# Positive_Rail.net
KiCad netlist of a schematic drawn in Altium Designer
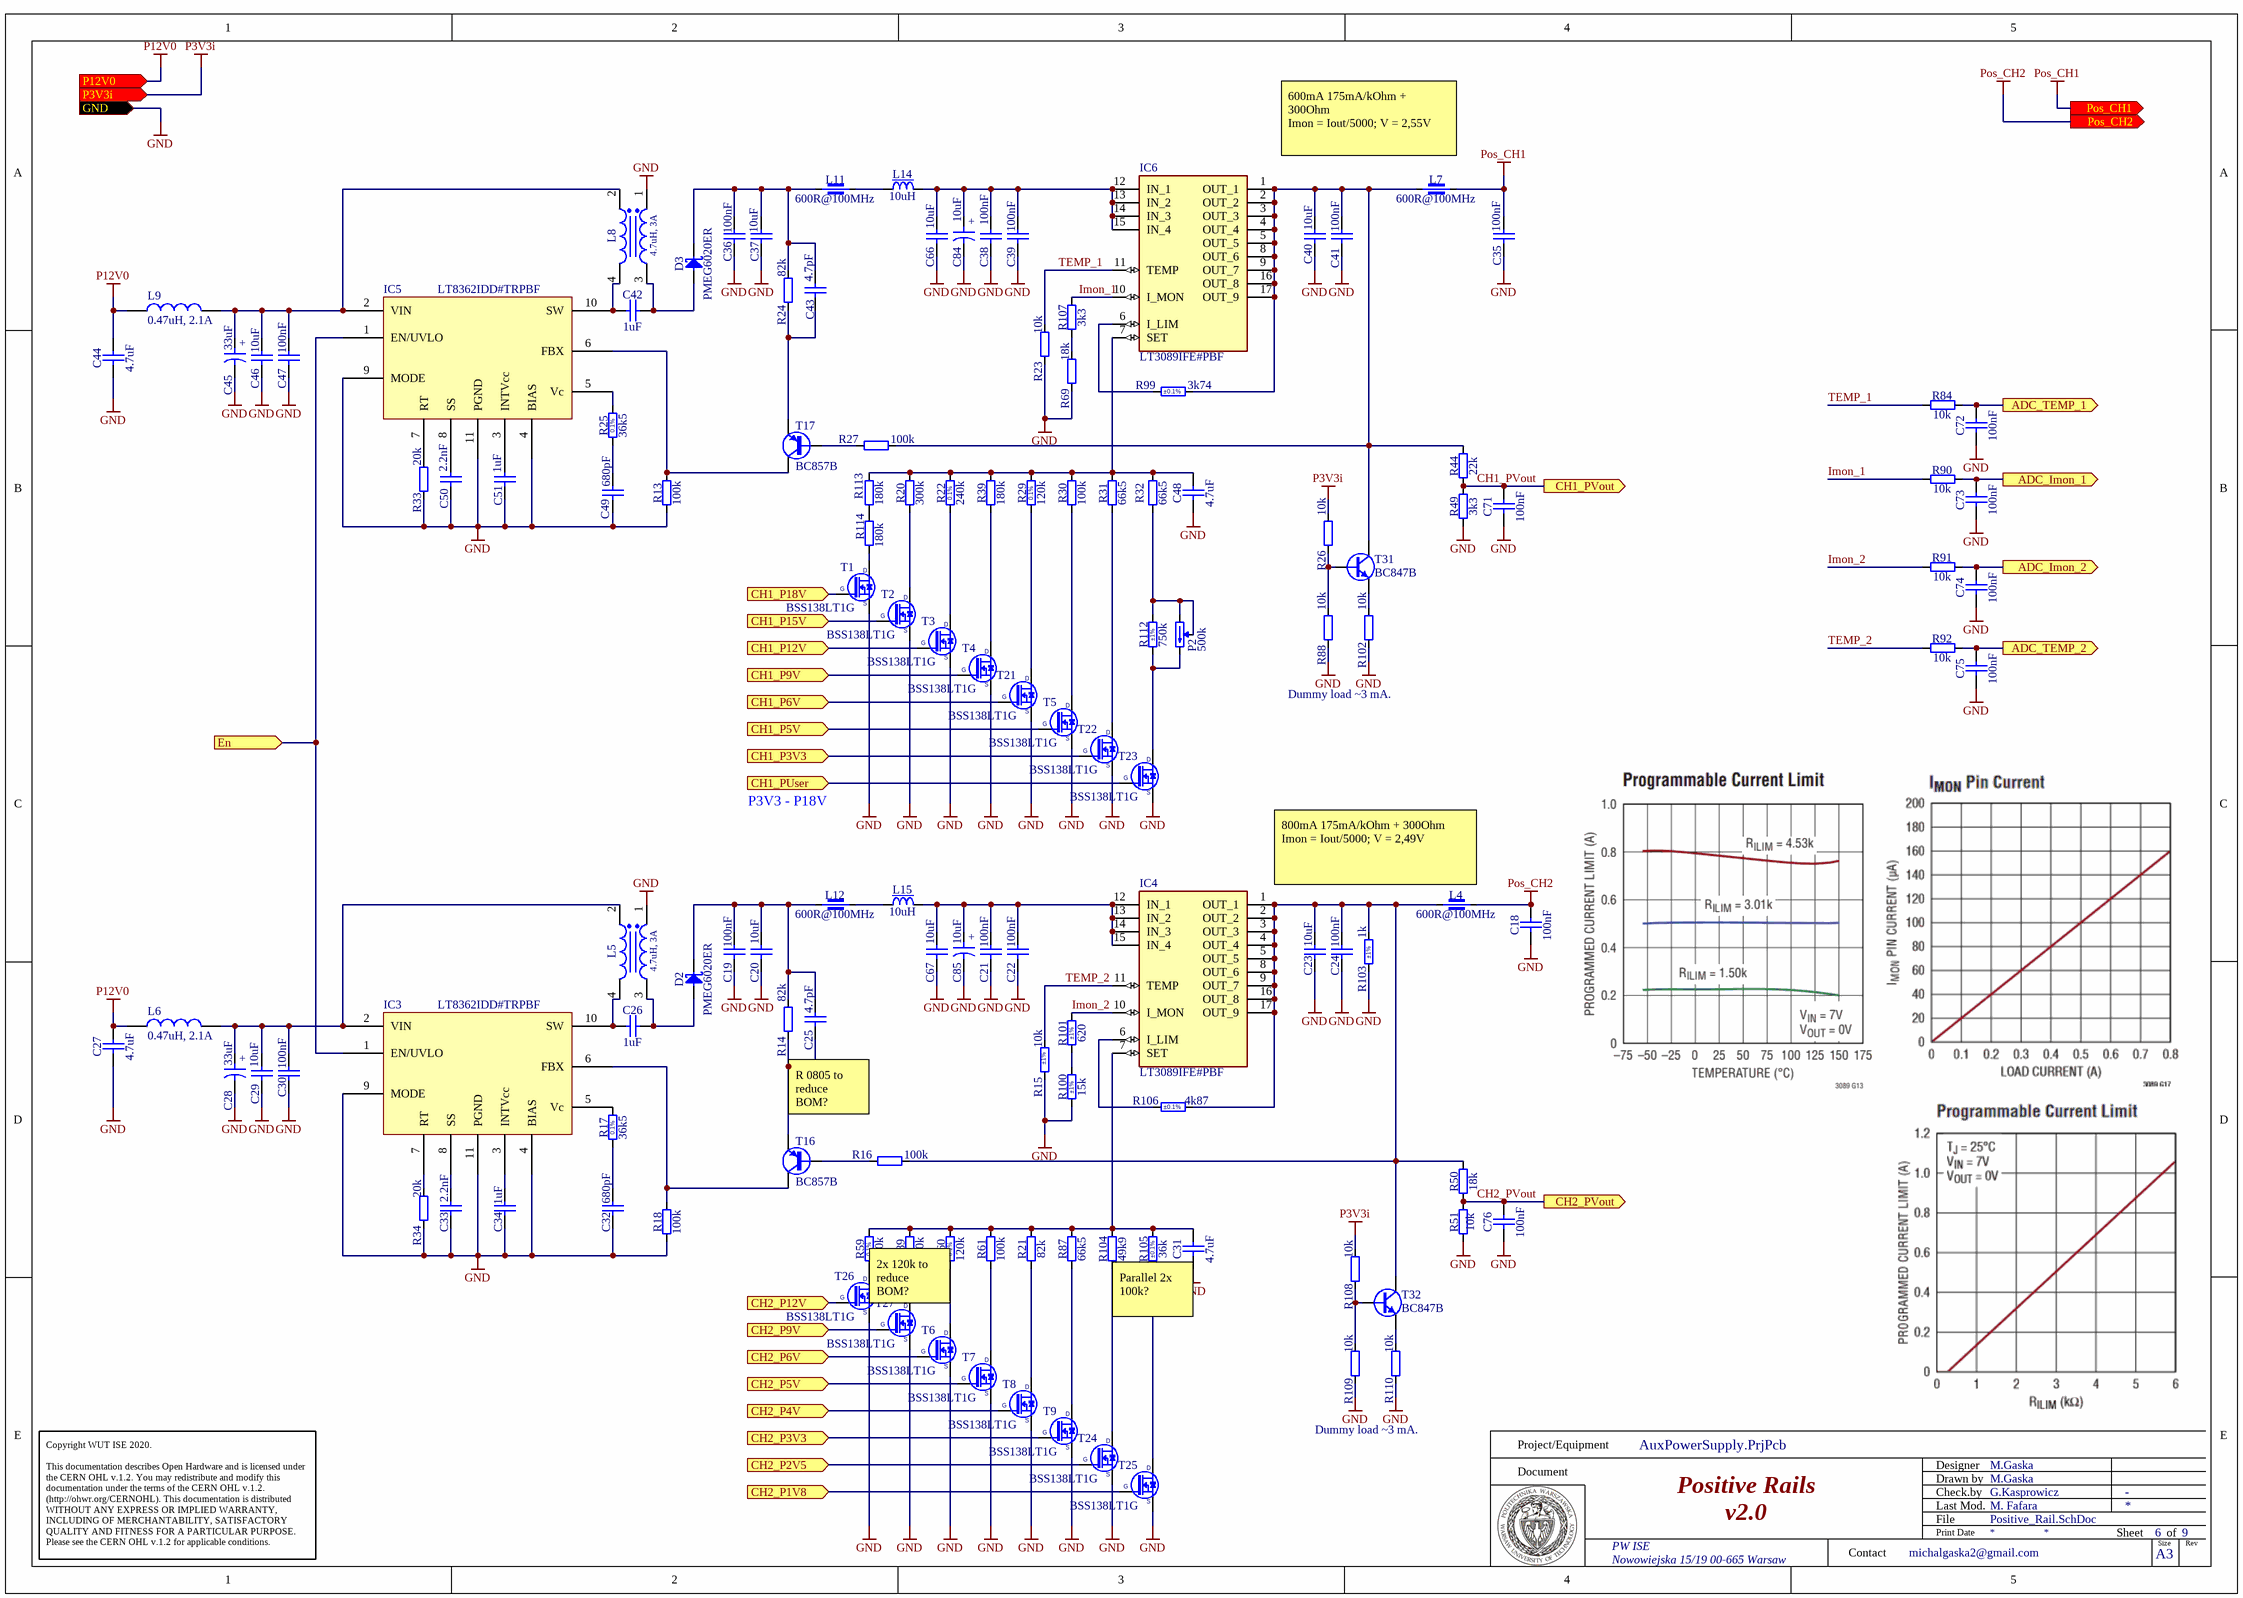
[diagram p0: Positive_Rail.SchDoc]

(export (version "E")
  (design (tool "Eeschema 10.0.6"))
  (components
    (comp (ref "C18")
      (value "100nF")
      (footprint "CAPC1608X87N")
      (description "Non-polarised capacitor")
      (fields
        (field (name "PART NUMBER") "CC0603_100NF_50V_10%_X5R")
        (field (name "VOLTAGE") "50V")
        (field (name "AUTHOR") "CERN DEM MR")
      )
      (libsource (lib "Capacitors") (part "Capacitor - non polarized"))
    )
    (comp (ref "C19")
      (value "100nF")
      (footprint "CAPC1608X87N")
      (description "Non-polarised capacitor")
      (fields
        (field (name "PART NUMBER") "CC0603_100NF_50V_10%_X5R")
        (field (name "VOLTAGE") "50V")
        (field (name "AUTHOR") "CERN DEM MR")
      )
      (libsource (lib "Capacitors") (part "Capacitor - non polarized"))
    )
    (comp (ref "C20")
      (value "10uF")
      (footprint "CAPC3216X190N")
      (description "Non-polarised capacitor")
      (fields
        (field (name "PART NUMBER") "CC1206_10UF_35V_10%_X7R_YUDEN_GMJ316BB7106KLHT")
        (field (name "VOLTAGE") "35V")
        (field (name "AUTHOR") "CERN DEM BC")
      )
      (libsource (lib "Capacitors") (part "Capacitor - non polarized"))
    )
    (comp (ref "C21")
      (value "100nF")
      (footprint "CAPC1608X87N")
      (description "Non-polarised capacitor")
      (fields
        (field (name "PART NUMBER") "CC0603_100NF_50V_10%_X5R")
        (field (name "VOLTAGE") "50V")
        (field (name "AUTHOR") "CERN DEM MR")
      )
      (libsource (lib "Capacitors") (part "Capacitor - non polarized"))
    )
    (comp (ref "C22")
      (value "100nF")
      (footprint "CAPC1608X87N")
      (description "Non-polarised capacitor")
      (fields
        (field (name "PART NUMBER") "CC0603_100NF_50V_10%_X5R")
        (field (name "VOLTAGE") "50V")
        (field (name "AUTHOR") "CERN DEM MR")
      )
      (libsource (lib "Capacitors") (part "Capacitor - non polarized"))
    )
    (comp (ref "C23")
      (value "10uF")
      (footprint "CAPC3216X190N")
      (description "Non-polarised capacitor")
      (fields
        (field (name "PART NUMBER") "CC1206_10UF_35V_10%_X7R_YUDEN_GMJ316BB7106KLHT")
        (field (name "VOLTAGE") "35V")
        (field (name "AUTHOR") "CERN DEM BC")
      )
      (libsource (lib "Capacitors") (part "Capacitor - non polarized"))
    )
    (comp (ref "C24")
      (value "100nF")
      (footprint "CAPC1608X87N")
      (description "Non-polarised capacitor")
      (fields
        (field (name "PART NUMBER") "CC0603_100NF_50V_10%_X5R")
        (field (name "VOLTAGE") "50V")
        (field (name "AUTHOR") "CERN DEM MR")
      )
      (libsource (lib "Capacitors") (part "Capacitor - non polarized"))
    )
    (comp (ref "C25")
      (value "4.7pF")
      (footprint "CAPC1608X87N")
      (description "Non-polarised capacitor")
      (fields
        (field (name "PART NUMBER") "CC0603_4.7PF_50V_0.25PF_NP0")
        (field (name "VOLTAGE") "50V")
        (field (name "AUTHOR") "CERN DEM JLC")
      )
      (libsource (lib "Capacitors") (part "Capacitor - non polarized"))
    )
    (comp (ref "C26")
      (value "1uF")
      (footprint "CAPC3216X140N")
      (description "Non-polarised capacitor")
      (fields
        (field (name "PART NUMBER") "CC1206_1UF_100V_10%_X7R")
        (field (name "VOLTAGE") "100V")
        (field (name "AUTHOR") "CERN DEM BC")
      )
      (libsource (lib "Capacitors") (part "Capacitor - non polarized"))
    )
    (comp (ref "C27")
      (value "4.7uF")
      (footprint "CAPC1608X90N")
      (description "Non-polarised capacitor")
      (fields
        (field (name "PART NUMBER") "CC0603_4.7UF_25V_10%_X5R")
        (field (name "VOLTAGE") "25V")
        (field (name "AUTHOR") "CERN DEM JLC")
      )
      (libsource (lib "Capacitors") (part "Capacitor - non polarized"))
    )
    (comp (ref "C28")
      (value "33uF")
      (footprint "CAPAE660X540N")
      (description "Polarised capacitor")
      (fields
        (field (name "PART NUMBER") "CAE660-540_33UF_35V_20%")
        (field (name "VOLTAGE") "35V")
        (field (name "AUTHOR") "CERN DEM JLC")
      )
      (libsource (lib "Capacitors") (part "Capacitor - polarized"))
    )
    (comp (ref "C29")
      (value "10uF")
      (footprint "CAPC3216X190N")
      (description "Non-polarised capacitor")
      (fields
        (field (name "PART NUMBER") "CC1206_10UF_35V_10%_X7R_YUDEN_GMJ316BB7106KLHT")
        (field (name "VOLTAGE") "35V")
        (field (name "AUTHOR") "CERN DEM BC")
      )
      (libsource (lib "Capacitors") (part "Capacitor - non polarized"))
    )
    (comp (ref "C30")
      (value "100nF")
      (footprint "CAPC1608X87N")
      (description "Non-polarised capacitor")
      (fields
        (field (name "PART NUMBER") "CC0603_100NF_50V_10%_X5R")
        (field (name "VOLTAGE") "50V")
        (field (name "AUTHOR") "CERN DEM MR")
      )
      (libsource (lib "Capacitors") (part "Capacitor - non polarized"))
    )
    (comp (ref "C31")
      (value "4.7uF")
      (footprint "CAPC1608X90N")
      (description "Non-polarised capacitor")
      (fields
        (field (name "PART NUMBER") "CC0603_4.7UF_25V_10%_X5R")
        (field (name "VOLTAGE") "25V")
        (field (name "AUTHOR") "CERN DEM JLC")
      )
      (libsource (lib "Capacitors") (part "Capacitor - non polarized"))
    )
    (comp (ref "C32")
      (value "680pF")
      (footprint "CAPC1608X87N")
      (description "Non-polarised capacitor")
      (fields
        (field (name "PART NUMBER") "CC0603_680PF_50V_5%_NP0")
        (field (name "VOLTAGE") "50V")
        (field (name "AUTHOR") "CERN DEM JLC")
      )
      (libsource (lib "Capacitors") (part "Capacitor - non polarized"))
    )
    (comp (ref "C33")
      (value "2.2nF")
      (footprint "CAPC1005X55N")
      (description "Non-polarised capacitor")
      (fields
        (field (name "PART NUMBER") "CC0402_2.2NF_50V_10%_X7R")
        (field (name "VOLTAGE") "50V")
        (field (name "AUTHOR") "CERN DEM JLC")
      )
      (libsource (lib "Capacitors") (part "Capacitor - non polarized"))
    )
    (comp (ref "C34")
      (value "1uF")
      (footprint "CAPC1608X87N")
      (description "Non-polarised capacitor")
      (fields
        (field (name "PART NUMBER") "CC0603_1UF_16V_10%_X7R")
        (field (name "VOLTAGE") "16V")
        (field (name "AUTHOR") "CERN DEM JLC")
      )
      (libsource (lib "Capacitors") (part "Capacitor - non polarized"))
    )
    (comp (ref "C35")
      (value "100nF")
      (footprint "CAPC1608X87N")
      (description "Non-polarised capacitor")
      (fields
        (field (name "PART NUMBER") "CC0603_100NF_50V_10%_X5R")
        (field (name "VOLTAGE") "50V")
        (field (name "AUTHOR") "CERN DEM MR")
      )
      (libsource (lib "Capacitors") (part "Capacitor - non polarized"))
    )
    (comp (ref "C36")
      (value "100nF")
      (footprint "CAPC1608X87N")
      (description "Non-polarised capacitor")
      (fields
        (field (name "PART NUMBER") "CC0603_100NF_50V_10%_X5R")
        (field (name "VOLTAGE") "50V")
        (field (name "AUTHOR") "CERN DEM MR")
      )
      (libsource (lib "Capacitors") (part "Capacitor - non polarized"))
    )
    (comp (ref "C37")
      (value "10uF")
      (footprint "CAPC3216X190N")
      (description "Non-polarised capacitor")
      (fields
        (field (name "PART NUMBER") "CC1206_10UF_35V_10%_X7R_YUDEN_GMJ316BB7106KLHT")
        (field (name "VOLTAGE") "35V")
        (field (name "AUTHOR") "CERN DEM BC")
      )
      (libsource (lib "Capacitors") (part "Capacitor - non polarized"))
    )
    (comp (ref "C38")
      (value "100nF")
      (footprint "CAPC1608X87N")
      (description "Non-polarised capacitor")
      (fields
        (field (name "PART NUMBER") "CC0603_100NF_50V_10%_X5R")
        (field (name "VOLTAGE") "50V")
        (field (name "AUTHOR") "CERN DEM MR")
      )
      (libsource (lib "Capacitors") (part "Capacitor - non polarized"))
    )
    (comp (ref "C39")
      (value "100nF")
      (footprint "CAPC1608X87N")
      (description "Non-polarised capacitor")
      (fields
        (field (name "PART NUMBER") "CC0603_100NF_50V_10%_X5R")
        (field (name "VOLTAGE") "50V")
        (field (name "AUTHOR") "CERN DEM MR")
      )
      (libsource (lib "Capacitors") (part "Capacitor - non polarized"))
    )
    (comp (ref "C40")
      (value "10uF")
      (footprint "CAPC3216X190N")
      (description "Non-polarised capacitor")
      (fields
        (field (name "PART NUMBER") "CC1206_10UF_35V_10%_X7R_YUDEN_GMJ316BB7106KLHT")
        (field (name "VOLTAGE") "35V")
        (field (name "AUTHOR") "CERN DEM BC")
      )
      (libsource (lib "Capacitors") (part "Capacitor - non polarized"))
    )
    (comp (ref "C41")
      (value "100nF")
      (footprint "CAPC1608X87N")
      (description "Non-polarised capacitor")
      (fields
        (field (name "PART NUMBER") "CC0603_100NF_50V_10%_X5R")
        (field (name "VOLTAGE") "50V")
        (field (name "AUTHOR") "CERN DEM MR")
      )
      (libsource (lib "Capacitors") (part "Capacitor - non polarized"))
    )
    (comp (ref "C42")
      (value "1uF")
      (footprint "CAPC3216X140N")
      (description "Non-polarised capacitor")
      (fields
        (field (name "PART NUMBER") "CC1206_1UF_100V_10%_X7R")
        (field (name "VOLTAGE") "100V")
        (field (name "AUTHOR") "CERN DEM BC")
      )
      (libsource (lib "Capacitors") (part "Capacitor - non polarized"))
    )
    (comp (ref "C43")
      (value "4.7pF")
      (footprint "CAPC1608X87N")
      (description "Non-polarised capacitor")
      (fields
        (field (name "PART NUMBER") "CC0603_4.7PF_50V_0.25PF_NP0")
        (field (name "VOLTAGE") "50V")
        (field (name "AUTHOR") "CERN DEM JLC")
      )
      (libsource (lib "Capacitors") (part "Capacitor - non polarized"))
    )
    (comp (ref "C44")
      (value "4.7uF")
      (footprint "CAPC1608X90N")
      (description "Non-polarised capacitor")
      (fields
        (field (name "PART NUMBER") "CC0603_4.7UF_25V_10%_X5R")
        (field (name "VOLTAGE") "25V")
        (field (name "AUTHOR") "CERN DEM JLC")
      )
      (libsource (lib "Capacitors") (part "Capacitor - non polarized"))
    )
    (comp (ref "C45")
      (value "33uF")
      (footprint "CAPAE660X540N")
      (description "Polarised capacitor")
      (fields
        (field (name "PART NUMBER") "CAE660-540_33UF_35V_20%")
        (field (name "VOLTAGE") "35V")
        (field (name "AUTHOR") "CERN DEM JLC")
      )
      (libsource (lib "Capacitors") (part "Capacitor - polarized"))
    )
    (comp (ref "C46")
      (value "10uF")
      (footprint "CAPC3216X190N")
      (description "Non-polarised capacitor")
      (fields
        (field (name "PART NUMBER") "CC1206_10UF_35V_10%_X7R_YUDEN_GMJ316BB7106KLHT")
        (field (name "VOLTAGE") "35V")
        (field (name "AUTHOR") "CERN DEM BC")
      )
      (libsource (lib "Capacitors") (part "Capacitor - non polarized"))
    )
    (comp (ref "C47")
      (value "100nF")
      (footprint "CAPC1608X87N")
      (description "Non-polarised capacitor")
      (fields
        (field (name "PART NUMBER") "CC0603_100NF_50V_10%_X5R")
        (field (name "VOLTAGE") "50V")
        (field (name "AUTHOR") "CERN DEM MR")
      )
      (libsource (lib "Capacitors") (part "Capacitor - non polarized"))
    )
    (comp (ref "C48")
      (value "4.7uF")
      (footprint "CAPC1608X90N")
      (description "Non-polarised capacitor")
      (fields
        (field (name "PART NUMBER") "CC0603_4.7UF_25V_10%_X5R")
        (field (name "VOLTAGE") "25V")
        (field (name "AUTHOR") "CERN DEM JLC")
      )
      (libsource (lib "Capacitors") (part "Capacitor - non polarized"))
    )
    (comp (ref "C49")
      (value "680pF")
      (footprint "CAPC1608X87N")
      (description "Non-polarised capacitor")
      (fields
        (field (name "PART NUMBER") "CC0603_680PF_50V_5%_NP0")
        (field (name "VOLTAGE") "50V")
        (field (name "AUTHOR") "CERN DEM JLC")
      )
      (libsource (lib "Capacitors") (part "Capacitor - non polarized"))
    )
    (comp (ref "C50")
      (value "2.2nF")
      (footprint "CAPC1005X55N")
      (description "Non-polarised capacitor")
      (fields
        (field (name "PART NUMBER") "CC0402_2.2NF_50V_10%_X7R")
        (field (name "VOLTAGE") "50V")
        (field (name "AUTHOR") "CERN DEM JLC")
      )
      (libsource (lib "Capacitors") (part "Capacitor - non polarized"))
    )
    (comp (ref "C51")
      (value "1uF")
      (footprint "CAPC1608X87N")
      (description "Non-polarised capacitor")
      (fields
        (field (name "PART NUMBER") "CC0603_1UF_16V_10%_X7R")
        (field (name "VOLTAGE") "16V")
        (field (name "AUTHOR") "CERN DEM JLC")
      )
      (libsource (lib "Capacitors") (part "Capacitor - non polarized"))
    )
    (comp (ref "C66")
      (value "10uF")
      (footprint "CAPC3216X190N")
      (description "Non-polarised capacitor")
      (fields
        (field (name "PART NUMBER") "CC1206_10UF_35V_10%_X7R_YUDEN_GMJ316BB7106KLHT")
        (field (name "VOLTAGE") "35V")
        (field (name "AUTHOR") "CERN DEM BC")
      )
      (libsource (lib "Capacitors") (part "Capacitor - non polarized"))
    )
    (comp (ref "C67")
      (value "10uF")
      (footprint "CAPC3216X190N")
      (description "Non-polarised capacitor")
      (fields
        (field (name "PART NUMBER") "CC1206_10UF_35V_10%_X7R_YUDEN_GMJ316BB7106KLHT")
        (field (name "VOLTAGE") "35V")
        (field (name "AUTHOR") "CERN DEM BC")
      )
      (libsource (lib "Capacitors") (part "Capacitor - non polarized"))
    )
    (comp (ref "C71")
      (value "100nF")
      (footprint "CAPC1608X87N")
      (description "Non-polarised capacitor")
      (fields
        (field (name "PART NUMBER") "CC0603_100NF_50V_10%_X5R")
        (field (name "VOLTAGE") "50V")
        (field (name "AUTHOR") "CERN DEM MR")
      )
      (libsource (lib "Capacitors") (part "Capacitor - non polarized"))
    )
    (comp (ref "C72")
      (value "100nF")
      (footprint "CAPC1608X87N")
      (description "Non-polarised capacitor")
      (fields
        (field (name "PART NUMBER") "CC0603_100NF_50V_10%_X5R")
        (field (name "VOLTAGE") "50V")
        (field (name "AUTHOR") "CERN DEM MR")
      )
      (libsource (lib "Capacitors") (part "Capacitor - non polarized"))
    )
    (comp (ref "C73")
      (value "100nF")
      (footprint "CAPC1608X87N")
      (description "Non-polarised capacitor")
      (fields
        (field (name "PART NUMBER") "CC0603_100NF_50V_10%_X5R")
        (field (name "VOLTAGE") "50V")
        (field (name "AUTHOR") "CERN DEM MR")
      )
      (libsource (lib "Capacitors") (part "Capacitor - non polarized"))
    )
    (comp (ref "C74")
      (value "100nF")
      (footprint "CAPC1608X87N")
      (description "Non-polarised capacitor")
      (fields
        (field (name "PART NUMBER") "CC0603_100NF_50V_10%_X5R")
        (field (name "VOLTAGE") "50V")
        (field (name "AUTHOR") "CERN DEM MR")
      )
      (libsource (lib "Capacitors") (part "Capacitor - non polarized"))
    )
    (comp (ref "C75")
      (value "100nF")
      (footprint "CAPC1608X87N")
      (description "Non-polarised capacitor")
      (fields
        (field (name "PART NUMBER") "CC0603_100NF_50V_10%_X5R")
        (field (name "VOLTAGE") "50V")
        (field (name "AUTHOR") "CERN DEM MR")
      )
      (libsource (lib "Capacitors") (part "Capacitor - non polarized"))
    )
    (comp (ref "C76")
      (value "100nF")
      (footprint "CAPC1608X87N")
      (description "Non-polarised capacitor")
      (fields
        (field (name "PART NUMBER") "CC0603_100NF_50V_10%_X5R")
        (field (name "VOLTAGE") "50V")
        (field (name "AUTHOR") "CERN DEM MR")
      )
      (libsource (lib "Capacitors") (part "Capacitor - non polarized"))
    )
    (comp (ref "C84")
      (value "10uF")
      (footprint "CAPMP6032X280N")
      (description "Polarised capacitor")
      (fields
        (field (name "PART NUMBER") "CTE6032-28_10UF_25V_10%_LESR0500")
        (field (name "VOLTAGE") "25V")
        (field (name "AUTHOR") "CERN DEM JLC")
      )
      (libsource (lib "Capacitors") (part "Capacitor - polarized"))
    )
    (comp (ref "C85")
      (value "10uF")
      (footprint "CAPMP6032X280N")
      (description "Polarised capacitor")
      (fields
        (field (name "PART NUMBER") "CTE6032-28_10UF_25V_10%_LESR0500")
        (field (name "VOLTAGE") "25V")
        (field (name "AUTHOR") "CERN DEM JLC")
      )
      (libsource (lib "Capacitors") (part "Capacitor - polarized"))
    )
    (comp (ref "D2")
      (value "PMEG6020ER")
      (footprint "SODFL3517X110N")
      (description "Schottky Diode")
      (fields
        (field (name "VOLTAGE") "60V")
        (field (name "POWER") "2A")
        (field (name "AUTHOR") "CERN DEM JMW")
      )
      (libsource (lib "ICs And Semiconductors") (part "Diode Schottky"))
    )
    (comp (ref "D3")
      (value "PMEG6020ER")
      (footprint "SODFL3517X110N")
      (description "Schottky Diode")
      (fields
        (field (name "VOLTAGE") "60V")
        (field (name "POWER") "2A")
        (field (name "AUTHOR") "CERN DEM JMW")
      )
      (libsource (lib "ICs And Semiconductors") (part "Diode Schottky"))
    )
    (comp (ref "IC3")
      (value "LT8362IDD#TRPBF")
      (footprint "SON50P300X300X80-11N-R160X240")
      (libsource (lib "MG_lib") (part "LT8362IDD#TRPBF"))
    )
    (comp (ref "IC4")
      (value "LT3089IFE#PBF")
      (footprint "SOP65P640X110-17N")
      (description "LDO Voltage Regulators 800mA 1x Res Rugged Lin Reg w/ Mon s")
      (fields (field (name "MOUSER PART NUMBER") "584-LT3089IFE#PBF"))
      (libsource (lib "Integrated_Library_LOADER") (part "LT3089IFE#PBF"))
    )
    (comp (ref "IC5")
      (value "LT8362IDD#TRPBF")
      (footprint "SON50P300X300X80-11N-R160X240")
      (libsource (lib "MG_lib") (part "LT8362IDD#TRPBF"))
    )
    (comp (ref "IC6")
      (value "LT3089IFE#PBF")
      (footprint "SOP65P640X110-17N")
      (description "LDO Voltage Regulators 800mA 1x Res Rugged Lin Reg w/ Mon s")
      (fields (field (name "MOUSER PART NUMBER") "584-LT3089IFE#PBF"))
      (libsource (lib "Integrated_Library_LOADER") (part "LT3089IFE#PBF"))
    )
    (comp (ref "L4")
      (value "600R@100MHz")
      (footprint "INDC2012X110N")
      (fields
        (field (name "PART NUMBER") "IND0805_WURTH_742792040")
        (field (name "POWER") "2A")
        (field (name "TOLERANCE") "±25%")
        (field (name "AUTHOR") "CERN DEM JLC")
      )
      (libsource (lib "Inductors & Transformers") (part "Ferrite Bead"))
    )
    (comp (ref "L5")
      (value "4.7uH, 3A")
      (footprint "WE-DD_1260")
      (description "WE-DD SMT Shielded Coupled Inductor, size 1260, 4.7uH, 3A")
      (fields
        (field (name "MANUFACTURER") "Wurth Elektronik")
        (field (name "MANUFACTURER PART NUMBER") "744871004")
      )
      (libsource (lib "744871470_Altium_WE-DD_rev20a") (part "744871004"))
    )
    (comp (ref "L6")
      (value "0.47uH, 2.1A")
      (footprint "WE-PMI_0806_H1")
      (description "WE-PMI Power Multilayer Inductor, size 0806, 0.47uH, 2.1A")
      (fields
        (field (name "MANUFACTURER") "Wurth Elektronik")
        (field (name "MANUFACTURER PART NUMBER") "74479876147")
      )
      (libsource (lib "Altium_WE-PMI_rev20a") (part "74479876147"))
    )
    (comp (ref "L7")
      (value "600R@100MHz")
      (footprint "INDC2012X110N")
      (fields
        (field (name "PART NUMBER") "IND0805_WURTH_742792040")
        (field (name "POWER") "2A")
        (field (name "TOLERANCE") "±25%")
        (field (name "AUTHOR") "CERN DEM JLC")
      )
      (libsource (lib "Inductors & Transformers") (part "Ferrite Bead"))
    )
    (comp (ref "L8")
      (value "4.7uH, 3A")
      (footprint "WE-DD_1260")
      (description "WE-DD SMT Shielded Coupled Inductor, size 1260, 4.7uH, 3A")
      (fields
        (field (name "MANUFACTURER") "Wurth Elektronik")
        (field (name "MANUFACTURER PART NUMBER") "744871004")
      )
      (libsource (lib "744871470_Altium_WE-DD_rev20a") (part "744871004"))
    )
    (comp (ref "L9")
      (value "0.47uH, 2.1A")
      (footprint "WE-PMI_0806_H1")
      (description "WE-PMI Power Multilayer Inductor, size 0806, 0.47uH, 2.1A")
      (fields
        (field (name "MANUFACTURER") "Wurth Elektronik")
        (field (name "MANUFACTURER PART NUMBER") "74479876147")
      )
      (libsource (lib "Altium_WE-PMI_rev20a") (part "74479876147"))
    )
    (comp (ref "L11")
      (value "600R@100MHz")
      (footprint "INDC2012X110N")
      (fields
        (field (name "PART NUMBER") "IND0805_WURTH_742792040")
        (field (name "POWER") "2A")
        (field (name "TOLERANCE") "±25%")
        (field (name "AUTHOR") "CERN DEM JLC")
      )
      (libsource (lib "Inductors & Transformers") (part "Ferrite Bead"))
    )
    (comp (ref "L12")
      (value "600R@100MHz")
      (footprint "INDC2012X110N")
      (fields
        (field (name "PART NUMBER") "IND0805_WURTH_742792040")
        (field (name "POWER") "2A")
        (field (name "TOLERANCE") "±25%")
        (field (name "AUTHOR") "CERN DEM JLC")
      )
      (libsource (lib "Inductors & Transformers") (part "Ferrite Bead"))
    )
    (comp (ref "L14")
      (value "10uH")
      (footprint "IND_BOURNS_PM43")
      (description "Inductor With Core")
      (fields
        (field (name "PART NUMBER") "IND_10UH_20%_BOURNS_PM43")
        (field (name "POWER") "1.15A")
        (field (name "AUTHOR") "CERN DEM JLC")
      )
      (libsource (lib "Inductors & Transformers") (part "Inductor With Magnetic core"))
    )
    (comp (ref "L15")
      (value "10uH")
      (footprint "IND_BOURNS_PM43")
      (description "Inductor With Core")
      (fields
        (field (name "PART NUMBER") "IND_10UH_20%_BOURNS_PM43")
        (field (name "POWER") "1.15A")
        (field (name "AUTHOR") "CERN DEM JLC")
      )
      (libsource (lib "Inductors & Transformers") (part "Inductor With Magnetic core"))
    )
    (comp (ref "P2")
      (value "500k")
      (footprint "Bourns_3059Y")
      (description "Trimmer, Cermet, 1W, 500000ohm, 400V, 10% +/-Tol, 100ppm/Cel, 22 Turn(s)")
      (fields (field (name "POWER") "1W") (field (name "TOLERANCE") "10%"))
      (libsource (lib "TechnoSystem Workspace") (part "Trimming Potentiometer"))
    )
    (comp (ref "R13")
      (value "100k")
      (footprint "RESC1608X55N")
      (description "Resistor - 1%")
      (fields
        (field (name "PART NUMBER") "R0603_100K_1%_0.1W_100PPM")
        (field (name "POWER") "0.1W")
        (field (name "AUTHOR") "CERN DEM JLC")
      )
      (libsource (lib "Resistors") (part "Resistor - 1%"))
    )
    (comp (ref "R14")
      (value "82k")
      (footprint "RESC1608X55N")
      (description "Resistor - 1%")
      (fields
        (field (name "PART NUMBER") "R0603_82K_1%_0.1W_100PPM")
        (field (name "POWER") "0.1W")
        (field (name "AUTHOR") "CERN DEM JLC")
      )
      (libsource (lib "Resistors") (part "Resistor - 1%"))
    )
    (comp (ref "R15")
      (value "10k")
      (footprint "RESC1608X55N")
      (description "Resistor - 1%")
      (fields
        (field (name "PART NUMBER") "R0603_10K_1%_0.1W_100PPM")
        (field (name "POWER") "0.1W")
        (field (name "TOLERANCE") "±1%")
        (field (name "AUTHOR") "CERN DEM JLC")
      )
      (libsource (lib "Resistors") (part "Resistor - 1%"))
    )
    (comp (ref "R16")
      (value "100k")
      (footprint "RESC1608X55N")
      (description "Resistor - 1%")
      (fields
        (field (name "PART NUMBER") "R0603_100K_1%_0.1W_100PPM")
        (field (name "POWER") "0.1W")
        (field (name "AUTHOR") "CERN DEM JLC")
      )
      (libsource (lib "Resistors") (part "Resistor - 1%"))
    )
    (comp (ref "R17")
      (value "36k5")
      (footprint "RESC1608X55N")
      (description "Resistor - 0.1%")
      (fields
        (field (name "PART NUMBER") "R0603_36K5_0.1%_0.063W_10PPM")
        (field (name "POWER") "0.063W")
        (field (name "AUTHOR") "CERN DEM JLC")
      )
      (libsource (lib "Resistors") (part "Resistor - 0.1%"))
    )
    (comp (ref "R18")
      (value "100k")
      (footprint "RESC1608X55N")
      (description "Resistor - 1%")
      (fields
        (field (name "PART NUMBER") "R0603_100K_1%_0.1W_100PPM")
        (field (name "POWER") "0.1W")
        (field (name "AUTHOR") "CERN DEM JLC")
      )
      (libsource (lib "Resistors") (part "Resistor - 1%"))
    )
    (comp (ref "R20")
      (value "300k")
      (footprint "RESC2012X60N")
      (description "Resistor - 1%")
      (fields
        (field (name "PART NUMBER") "R0805_300K_1%_0.125W_100PPM")
        (field (name "POWER") "0.125W")
        (field (name "AUTHOR") "CERN DEM JLC")
      )
      (libsource (lib "Resistors") (part "Resistor - 1%"))
    )
    (comp (ref "R21")
      (value "82k")
      (footprint "RESC2012X60N")
      (description "Resistor - 1%")
      (fields
        (field (name "PART NUMBER") "R0805_82K_1%_0.125W_100PPM")
        (field (name "POWER") "0.125W")
        (field (name "AUTHOR") "CERN DEM JLC")
      )
      (libsource (lib "Resistors") (part "Resistor - 1%"))
    )
    (comp (ref "R22")
      (value "240k")
      (footprint "RESC2012X60N")
      (description "Resistor - 0.1%")
      (fields
        (field (name "PART NUMBER") "R0805_240K_0.1%_0.1W_10PPM")
        (field (name "POWER") "0.1W")
        (field (name "AUTHOR") "CERN DEM JLC")
      )
      (libsource (lib "Resistors") (part "Resistor - 0.1%"))
    )
    (comp (ref "R23")
      (value "10k")
      (footprint "RESC1608X55N")
      (description "Resistor - 1%")
      (fields
        (field (name "PART NUMBER") "R0603_10K_1%_0.1W_100PPM")
        (field (name "POWER") "0.1W")
        (field (name "AUTHOR") "CERN DEM JLC")
      )
      (libsource (lib "Resistors") (part "Resistor - 1%"))
    )
    (comp (ref "R24")
      (value "82k")
      (footprint "RESC1608X55N")
      (description "Resistor - 1%")
      (fields
        (field (name "PART NUMBER") "R0603_82K_1%_0.1W_100PPM")
        (field (name "POWER") "0.1W")
        (field (name "AUTHOR") "CERN DEM JLC")
      )
      (libsource (lib "Resistors") (part "Resistor - 1%"))
    )
    (comp (ref "R25")
      (value "36k5")
      (footprint "RESC1608X55N")
      (description "Resistor - 0.1%")
      (fields
        (field (name "PART NUMBER") "R0603_36K5_0.1%_0.063W_10PPM")
        (field (name "POWER") "0.063W")
        (field (name "AUTHOR") "CERN DEM JLC")
      )
      (libsource (lib "Resistors") (part "Resistor - 0.1%"))
    )
    (comp (ref "R26")
      (value "10k")
      (footprint "RESC1608X55N")
      (description "Resistor - 1%")
      (fields
        (field (name "PART NUMBER") "R0603_10K_1%_0.1W_100PPM")
        (field (name "POWER") "0.1W")
        (field (name "AUTHOR") "CERN DEM JLC")
      )
      (libsource (lib "Resistors") (part "Resistor - 1%"))
    )
    (comp (ref "R27")
      (value "100k")
      (footprint "RESC1608X55N")
      (description "Resistor - 1%")
      (fields
        (field (name "PART NUMBER") "R0603_100K_1%_0.1W_100PPM")
        (field (name "POWER") "0.1W")
        (field (name "AUTHOR") "CERN DEM JLC")
      )
      (libsource (lib "Resistors") (part "Resistor - 1%"))
    )
    (comp (ref "R29")
      (value "120k")
      (footprint "RESC2012X60N")
      (description "Resistor - 0.1%")
      (fields
        (field (name "PART NUMBER") "R0805_120K_0.1%_0.125W_25PPM")
        (field (name "POWER") "0.125W")
        (field (name "AUTHOR") "CERN DEM JLC")
      )
      (libsource (lib "Resistors") (part "Resistor - 0.1%"))
    )
    (comp (ref "R30")
      (value "100k")
      (footprint "RESC2012X60N")
      (description "Resistor - 0.1%")
      (fields
        (field (name "PART NUMBER") "R0805_100K_0.1%_0.1W_10PPM")
        (field (name "POWER") "0.1W")
        (field (name "AUTHOR") "CERN DEM JLC")
      )
      (libsource (lib "") (part "Resistor - 0.1%_1"))
    )
    (comp (ref "R31")
      (value "66k5")
      (footprint "RESC2012X60N")
      (description "Resistor - 0.1%")
      (fields
        (field (name "PART NUMBER") "R0805_66K5_0.1%_0.1W_10PPM")
        (field (name "POWER") "0.1W")
        (field (name "AUTHOR") "CERN DEM JLC")
      )
      (libsource (lib "") (part "Resistor - 0.1%_1"))
    )
    (comp (ref "R32")
      (value "66k5")
      (footprint "RESC2012X60N")
      (description "Resistor - 0.1%")
      (fields
        (field (name "PART NUMBER") "R0805_66K5_0.1%_0.1W_10PPM")
        (field (name "POWER") "0.1W")
        (field (name "AUTHOR") "CERN DEM JLC")
      )
      (libsource (lib "") (part "Resistor - 0.1%_1"))
    )
    (comp (ref "R33")
      (value "20k")
      (footprint "RESC1608X55N")
      (description "Resistor - 1%")
      (fields
        (field (name "PART NUMBER") "R0603_20K_1%_0.1W_100PPM")
        (field (name "POWER") "0.1W")
        (field (name "AUTHOR") "CERN DEM JLC")
      )
      (libsource (lib "Resistors") (part "Resistor - 1%"))
    )
    (comp (ref "R34")
      (value "20k")
      (footprint "RESC1608X55N")
      (description "Resistor - 1%")
      (fields
        (field (name "PART NUMBER") "R0603_20K_1%_0.1W_100PPM")
        (field (name "POWER") "0.1W")
        (field (name "AUTHOR") "CERN DEM JLC")
      )
      (libsource (lib "Resistors") (part "Resistor - 1%"))
    )
    (comp (ref "R39")
      (value "180k")
      (footprint "RESC2012X60N")
      (description "Resistor - 1%")
      (fields
        (field (name "PART NUMBER") "R0805_180K_1%_0.125W_100PPM")
        (field (name "POWER") "0.125W")
        (field (name "AUTHOR") "CERN DEM JLC")
      )
      (libsource (lib "Resistors") (part "Resistor - 1%"))
    )
    (comp (ref "R44")
      (value "22k")
      (footprint "RESC1608X55N")
      (description "Resistor - 1%")
      (fields
        (field (name "PART NUMBER") "R0603_22K_1%_0.1W_100PPM")
        (field (name "POWER") "0.1W")
        (field (name "AUTHOR") "CERN DEM JLC")
      )
      (libsource (lib "Resistors") (part "Resistor - 1%"))
    )
    (comp (ref "R49")
      (value "3k3")
      (footprint "RESC1608X55N")
      (description "Resistor - 1%")
      (fields
        (field (name "PART NUMBER") "R0603_3K3_1%_0.1W_100PPM")
        (field (name "POWER") "0.1W")
        (field (name "AUTHOR") "CERN DEM JLC")
      )
      (libsource (lib "Resistors") (part "Resistor - 1%"))
    )
    (comp (ref "R50")
      (value "18k")
      (footprint "RESC1608X55N")
      (description "Resistor - 1%")
      (fields
        (field (name "PART NUMBER") "R0603_18K_1%_0.1W_100PPM")
        (field (name "POWER") "0.1W")
        (field (name "AUTHOR") "CERN DEM JLC")
      )
      (libsource (lib "Resistors") (part "Resistor - 1%"))
    )
    (comp (ref "R51")
      (value "10k")
      (footprint "RESC1608X55N")
      (description "Resistor - 1%")
      (fields
        (field (name "PART NUMBER") "R0603_10K_1%_0.1W_100PPM")
        (field (name "POWER") "0.1W")
        (field (name "AUTHOR") "CERN DEM JLC")
      )
      (libsource (lib "Resistors") (part "Resistor - 1%"))
    )
    (comp (ref "R59")
      (value "240k")
      (footprint "RESC2012X60N")
      (description "Resistor - 0.1%")
      (fields
        (field (name "PART NUMBER") "R0805_240K_0.1%_0.1W_10PPM")
        (field (name "POWER") "0.1W")
        (field (name "AUTHOR") "CERN DEM JLC")
      )
      (libsource (lib "Resistors") (part "Resistor - 0.1%"))
    )
    (comp (ref "R60")
      (value "120k")
      (footprint "RESC2012X60N")
      (description "Resistor - 0.1%")
      (fields
        (field (name "PART NUMBER") "R0805_120K_0.1%_0.125W_25PPM")
        (field (name "POWER") "0.125W")
        (field (name "AUTHOR") "CERN DEM JLC")
      )
      (libsource (lib "Resistors") (part "Resistor - 0.1%"))
    )
    (comp (ref "R61")
      (value "100k")
      (footprint "RESC2012X60N")
      (description "Resistor - 0.1%")
      (fields
        (field (name "PART NUMBER") "R0805_100K_0.1%_0.1W_10PPM")
        (field (name "POWER") "0.1W")
        (field (name "AUTHOR") "CERN DEM JLC")
      )
      (libsource (lib "") (part "Resistor - 0.1%_1"))
    )
    (comp (ref "R69")
      (value "18k")
      (footprint "RESC1608X55N")
      (description "Resistor - 1%")
      (fields
        (field (name "PART NUMBER") "R0603_18K_1%_0.1W_100PPM")
        (field (name "POWER") "0.1W")
        (field (name "AUTHOR") "CERN DEM JLC")
      )
      (libsource (lib "Resistors") (part "Resistor - 1%"))
    )
    (comp (ref "R84")
      (value "10k")
      (footprint "RESC1608X55N")
      (description "Resistor - 1%")
      (fields
        (field (name "PART NUMBER") "R0603_10K_1%_0.1W_100PPM")
        (field (name "POWER") "0.1W")
        (field (name "AUTHOR") "CERN DEM JLC")
      )
      (libsource (lib "Resistors") (part "Resistor - 1%"))
    )
    (comp (ref "R87")
      (value "66k5")
      (footprint "RESC2012X60N")
      (description "Resistor - 0.1%")
      (fields
        (field (name "PART NUMBER") "R0805_66K5_0.1%_0.1W_10PPM")
        (field (name "POWER") "0.1W")
        (field (name "AUTHOR") "CERN DEM JLC")
      )
      (libsource (lib "") (part "Resistor - 0.1%_1"))
    )
    (comp (ref "R88")
      (value "10k")
      (footprint "RESC1608X55N")
      (description "Resistor - 1%")
      (fields
        (field (name "PART NUMBER") "R0603_10K_1%_0.1W_100PPM")
        (field (name "POWER") "0.1W")
        (field (name "AUTHOR") "CERN DEM JLC")
      )
      (libsource (lib "Resistors") (part "Resistor - 1%"))
    )
    (comp (ref "R89")
      (value "180k")
      (footprint "RESC2012X60N")
      (description "Resistor - 1%")
      (fields
        (field (name "PART NUMBER") "R0805_180K_1%_0.125W_100PPM")
        (field (name "POWER") "0.125W")
        (field (name "AUTHOR") "CERN DEM JLC")
      )
      (libsource (lib "Resistors") (part "Resistor - 1%"))
    )
    (comp (ref "R90")
      (value "10k")
      (footprint "RESC1608X55N")
      (description "Resistor - 1%")
      (fields
        (field (name "PART NUMBER") "R0603_10K_1%_0.1W_100PPM")
        (field (name "POWER") "0.1W")
        (field (name "AUTHOR") "CERN DEM JLC")
      )
      (libsource (lib "Resistors") (part "Resistor - 1%"))
    )
    (comp (ref "R91")
      (value "10k")
      (footprint "RESC1608X55N")
      (description "Resistor - 1%")
      (fields
        (field (name "PART NUMBER") "R0603_10K_1%_0.1W_100PPM")
        (field (name "POWER") "0.1W")
        (field (name "AUTHOR") "CERN DEM JLC")
      )
      (libsource (lib "Resistors") (part "Resistor - 1%"))
    )
    (comp (ref "R92")
      (value "10k")
      (footprint "RESC1608X55N")
      (description "Resistor - 1%")
      (fields
        (field (name "PART NUMBER") "R0603_10K_1%_0.1W_100PPM")
        (field (name "POWER") "0.1W")
        (field (name "AUTHOR") "CERN DEM JLC")
      )
      (libsource (lib "Resistors") (part "Resistor - 1%"))
    )
    (comp (ref "R99")
      (value "3k74")
      (footprint "RESC1608X55N")
      (description "Resistor - 0.1%")
      (fields
        (field (name "TOLERANCE") "±0.1%")
        (field (name "PART NUMBER") "R0603_3K74_0.1%_0.063W_10PPM")
        (field (name "POWER") "0.063W")
        (field (name "AUTHOR") "CERN DEM JLC")
      )
      (libsource (lib "Resistors") (part "Resistor - 0.1%"))
    )
    (comp (ref "R100")
      (value "15k")
      (footprint "RESC1608X55N")
      (description "Resistor - 1%")
      (fields
        (field (name "TOLERANCE") "±1%")
        (field (name "PART NUMBER") "R0603_15K_1%_0.1W_100PPM")
        (field (name "POWER") "0.1W")
        (field (name "AUTHOR") "CERN DEM JMW")
      )
      (libsource (lib "Resistors") (part "Resistor - 1%"))
    )
    (comp (ref "R101")
      (value "620")
      (footprint "RESC1608X55N")
      (description "Resistor - 1%")
      (fields
        (field (name "TOLERANCE") "±1%")
        (field (name "PART NUMBER") "R0603_620R_1%_0.1W_100PPM")
        (field (name "POWER") "0.1W")
        (field (name "AUTHOR") "CERN DEM JLC")
      )
      (libsource (lib "Resistors") (part "Resistor - 1%"))
    )
    (comp (ref "R102")
      (value "10k")
      (footprint "RESC1608X55N")
      (description "Resistor - 1%")
      (fields
        (field (name "PART NUMBER") "R0603_10K_1%_0.1W_100PPM")
        (field (name "POWER") "0.1W")
        (field (name "AUTHOR") "CERN DEM JLC")
      )
      (libsource (lib "Resistors") (part "Resistor - 1%"))
    )
    (comp (ref "R103")
      (value "1k")
      (footprint "RESC3216X65N")
      (description "Resistor - 1%")
      (fields
        (field (name "TOLERANCE") "±1%")
        (field (name "PART NUMBER") "R1206_1K_1%_0.75W_100PPM_VISHAY_CRCW-HP e3")
        (field (name "POWER") "0.75W")
        (field (name "AUTHOR") "CERN DEM JLC")
      )
      (libsource (lib "Resistors") (part "Resistor - 1%"))
    )
    (comp (ref "R104")
      (value "49k9")
      (footprint "RESC2012X60N")
      (description "Resistor - 0.1%")
      (fields
        (field (name "PART NUMBER") "R0805_49K9_0.1%_0.1W_10PPM")
        (field (name "POWER") "0.1W")
        (field (name "AUTHOR") "CERN DEM JLC")
      )
      (libsource (lib "") (part "Resistor - 0.1%_1"))
    )
    (comp (ref "R105")
      (value "36k")
      (footprint "RESC2012X60N")
      (description "Resistor - 0.1%")
      (fields
        (field (name "TOLERANCE") "±0.1%")
        (field (name "PART NUMBER") "R0805_36K_0.1%_0.125W_25PPM")
        (field (name "POWER") "0.125W")
        (field (name "AUTHOR") "CERN DEM JLC")
      )
      (libsource (lib "") (part "Resistor - 0.1%_1"))
    )
    (comp (ref "R106")
      (value "4k87")
      (footprint "RESC1608X55N")
      (description "Resistor - 0.1%")
      (fields
        (field (name "TOLERANCE") "±0.1%")
        (field (name "PART NUMBER") "R0603_4K87_0.1%_0.063W_10PPM")
        (field (name "POWER") "0.063W")
        (field (name "AUTHOR") "CERN DEM JLC")
      )
      (libsource (lib "Resistors") (part "Resistor - 0.1%"))
    )
    (comp (ref "R107")
      (value "3k3")
      (footprint "RESC1608X55N")
      (description "Resistor - 1%")
      (fields
        (field (name "PART NUMBER") "R0603_3K3_1%_0.1W_100PPM")
        (field (name "POWER") "0.1W")
        (field (name "AUTHOR") "CERN DEM JLC")
      )
      (libsource (lib "Resistors") (part "Resistor - 1%"))
    )
    (comp (ref "R108")
      (value "10k")
      (footprint "RESC1608X55N")
      (description "Resistor - 1%")
      (fields
        (field (name "PART NUMBER") "R0603_10K_1%_0.1W_100PPM")
        (field (name "POWER") "0.1W")
        (field (name "AUTHOR") "CERN DEM JLC")
      )
      (libsource (lib "Resistors") (part "Resistor - 1%"))
    )
    (comp (ref "R109")
      (value "10k")
      (footprint "RESC1608X55N")
      (description "Resistor - 1%")
      (fields
        (field (name "PART NUMBER") "R0603_10K_1%_0.1W_100PPM")
        (field (name "POWER") "0.1W")
        (field (name "AUTHOR") "CERN DEM JLC")
      )
      (libsource (lib "Resistors") (part "Resistor - 1%"))
    )
    (comp (ref "R110")
      (value "10k")
      (footprint "RESC1608X55N")
      (description "Resistor - 1%")
      (fields
        (field (name "PART NUMBER") "R0603_10K_1%_0.1W_100PPM")
        (field (name "POWER") "0.1W")
        (field (name "AUTHOR") "CERN DEM JLC")
      )
      (libsource (lib "Resistors") (part "Resistor - 1%"))
    )
    (comp (ref "R112")
      (value "750k")
      (footprint "RESC2012X60N")
      (description "Resistor - 1%")
      (fields
        (field (name "TOLERANCE") "±1%")
        (field (name "PART NUMBER") "R0805_750K_1%_0.125W_100PPM")
        (field (name "POWER") "0.125W")
        (field (name "AUTHOR") "CERN DEM JLC")
      )
      (libsource (lib "Resistors") (part "Resistor - 1%"))
    )
    (comp (ref "R113")
      (value "180k")
      (footprint "RESC2012X60N")
      (description "Resistor - 1%")
      (fields
        (field (name "PART NUMBER") "R0805_180K_1%_0.125W_100PPM")
        (field (name "POWER") "0.125W")
        (field (name "AUTHOR") "CERN DEM JLC")
      )
      (libsource (lib "Resistors") (part "Resistor - 1%"))
    )
    (comp (ref "R114")
      (value "180k")
      (footprint "RESC2012X60N")
      (description "Resistor - 1%")
      (fields
        (field (name "PART NUMBER") "R0805_180K_1%_0.125W_100PPM")
        (field (name "POWER") "0.125W")
        (field (name "AUTHOR") "CERN DEM JLC")
      )
      (libsource (lib "Resistors") (part "Resistor - 1%"))
    )
    (comp (ref "T1")
      (value "BSS138LT1G")
      (footprint "SOT95P240X110-3N")
      (description "N-CHANNEL MOSFET WITH DIODE")
      (fields
        (field (name "MANUFACTURER") "ON SEMICONDUCTOR")
        (field (name "MANUFACTURER PART NUMBER") "BSS138L")
        (field (name "AUTHOR") "CERN DEM JLC")
      )
      (libsource (lib "ICs And Semiconductors") (part "N-MOSFET-D 1G 2S 3D"))
    )
    (comp (ref "T2")
      (value "BSS138LT1G")
      (footprint "SOT95P240X110-3N")
      (description "N-CHANNEL MOSFET WITH DIODE")
      (fields
        (field (name "MANUFACTURER") "ON SEMICONDUCTOR")
        (field (name "MANUFACTURER PART NUMBER") "BSS138L")
        (field (name "AUTHOR") "CERN DEM JLC")
      )
      (libsource (lib "ICs And Semiconductors") (part "N-MOSFET-D 1G 2S 3D"))
    )
    (comp (ref "T3")
      (value "BSS138LT1G")
      (footprint "SOT95P240X110-3N")
      (description "N-CHANNEL MOSFET WITH DIODE")
      (fields
        (field (name "MANUFACTURER") "ON SEMICONDUCTOR")
        (field (name "MANUFACTURER PART NUMBER") "BSS138L")
        (field (name "AUTHOR") "CERN DEM JLC")
      )
      (libsource (lib "ICs And Semiconductors") (part "N-MOSFET-D 1G 2S 3D"))
    )
    (comp (ref "T4")
      (value "BSS138LT1G")
      (footprint "SOT95P240X110-3N")
      (description "N-CHANNEL MOSFET WITH DIODE")
      (fields
        (field (name "MANUFACTURER") "ON SEMICONDUCTOR")
        (field (name "MANUFACTURER PART NUMBER") "BSS138L")
        (field (name "AUTHOR") "CERN DEM JLC")
      )
      (libsource (lib "ICs And Semiconductors") (part "N-MOSFET-D 1G 2S 3D"))
    )
    (comp (ref "T5")
      (value "BSS138LT1G")
      (footprint "SOT95P240X110-3N")
      (description "N-CHANNEL MOSFET WITH DIODE")
      (fields
        (field (name "MANUFACTURER") "ON SEMICONDUCTOR")
        (field (name "MANUFACTURER PART NUMBER") "BSS138L")
        (field (name "AUTHOR") "CERN DEM JLC")
      )
      (libsource (lib "ICs And Semiconductors") (part "N-MOSFET-D 1G 2S 3D"))
    )
    (comp (ref "T6")
      (value "BSS138LT1G")
      (footprint "SOT95P240X110-3N")
      (description "N-CHANNEL MOSFET WITH DIODE")
      (fields
        (field (name "MANUFACTURER") "ON SEMICONDUCTOR")
        (field (name "MANUFACTURER PART NUMBER") "BSS138L")
        (field (name "AUTHOR") "CERN DEM JLC")
      )
      (libsource (lib "ICs And Semiconductors") (part "N-MOSFET-D 1G 2S 3D"))
    )
    (comp (ref "T7")
      (value "BSS138LT1G")
      (footprint "SOT95P240X110-3N")
      (description "N-CHANNEL MOSFET WITH DIODE")
      (fields
        (field (name "MANUFACTURER") "ON SEMICONDUCTOR")
        (field (name "MANUFACTURER PART NUMBER") "BSS138L")
        (field (name "AUTHOR") "CERN DEM JLC")
      )
      (libsource (lib "ICs And Semiconductors") (part "N-MOSFET-D 1G 2S 3D"))
    )
    (comp (ref "T8")
      (value "BSS138LT1G")
      (footprint "SOT95P240X110-3N")
      (description "N-CHANNEL MOSFET WITH DIODE")
      (fields
        (field (name "MANUFACTURER") "ON SEMICONDUCTOR")
        (field (name "MANUFACTURER PART NUMBER") "BSS138L")
        (field (name "AUTHOR") "CERN DEM JLC")
      )
      (libsource (lib "ICs And Semiconductors") (part "N-MOSFET-D 1G 2S 3D"))
    )
    (comp (ref "T9")
      (value "BSS138LT1G")
      (footprint "SOT95P240X110-3N")
      (description "N-CHANNEL MOSFET WITH DIODE")
      (fields
        (field (name "MANUFACTURER") "ON SEMICONDUCTOR")
        (field (name "MANUFACTURER PART NUMBER") "BSS138L")
        (field (name "AUTHOR") "CERN DEM JLC")
      )
      (libsource (lib "ICs And Semiconductors") (part "N-MOSFET-D 1G 2S 3D"))
    )
    (comp (ref "T16")
      (value "BC857B")
      (footprint "SOT95P230X110-3N")
      (description "PNP Transistor")
      (fields (field (name "MANUFACTURER") "NXP SEMICONDUCTORS") (field (name "AUTHOR") "CERN DEM JLC"))
      (libsource (lib "ICs And Semiconductors") (part "PNP B1 E2 C3"))
    )
    (comp (ref "T17")
      (value "BC857B")
      (footprint "SOT95P230X110-3N")
      (description "PNP Transistor")
      (fields (field (name "MANUFACTURER") "NXP SEMICONDUCTORS") (field (name "AUTHOR") "CERN DEM JLC"))
      (libsource (lib "ICs And Semiconductors") (part "PNP B1 E2 C3"))
    )
    (comp (ref "T21")
      (value "BSS138LT1G")
      (footprint "SOT95P240X110-3N")
      (description "N-CHANNEL MOSFET WITH DIODE")
      (fields
        (field (name "MANUFACTURER") "ON SEMICONDUCTOR")
        (field (name "MANUFACTURER PART NUMBER") "BSS138L")
        (field (name "AUTHOR") "CERN DEM JLC")
      )
      (libsource (lib "ICs And Semiconductors") (part "N-MOSFET-D 1G 2S 3D"))
    )
    (comp (ref "T22")
      (value "BSS138LT1G")
      (footprint "SOT95P240X110-3N")
      (description "N-CHANNEL MOSFET WITH DIODE")
      (fields
        (field (name "MANUFACTURER") "ON SEMICONDUCTOR")
        (field (name "MANUFACTURER PART NUMBER") "BSS138L")
        (field (name "AUTHOR") "CERN DEM JLC")
      )
      (libsource (lib "ICs And Semiconductors") (part "N-MOSFET-D 1G 2S 3D"))
    )
    (comp (ref "T23")
      (value "BSS138LT1G")
      (footprint "SOT95P240X110-3N")
      (description "N-CHANNEL MOSFET WITH DIODE")
      (fields
        (field (name "MANUFACTURER") "ON SEMICONDUCTOR")
        (field (name "MANUFACTURER PART NUMBER") "BSS138L")
        (field (name "AUTHOR") "CERN DEM JLC")
      )
      (libsource (lib "ICs And Semiconductors") (part "N-MOSFET-D 1G 2S 3D"))
    )
    (comp (ref "T24")
      (value "BSS138LT1G")
      (footprint "SOT95P240X110-3N")
      (description "N-CHANNEL MOSFET WITH DIODE")
      (fields
        (field (name "MANUFACTURER") "ON SEMICONDUCTOR")
        (field (name "MANUFACTURER PART NUMBER") "BSS138L")
        (field (name "AUTHOR") "CERN DEM JLC")
      )
      (libsource (lib "ICs And Semiconductors") (part "N-MOSFET-D 1G 2S 3D"))
    )
    (comp (ref "T25")
      (value "BSS138LT1G")
      (footprint "SOT95P240X110-3N")
      (description "N-CHANNEL MOSFET WITH DIODE")
      (fields
        (field (name "MANUFACTURER") "ON SEMICONDUCTOR")
        (field (name "MANUFACTURER PART NUMBER") "BSS138L")
        (field (name "AUTHOR") "CERN DEM JLC")
      )
      (libsource (lib "ICs And Semiconductors") (part "N-MOSFET-D 1G 2S 3D"))
    )
    (comp (ref "T26")
      (value "BSS138LT1G")
      (footprint "SOT95P240X110-3N")
      (description "N-CHANNEL MOSFET WITH DIODE")
      (fields
        (field (name "MANUFACTURER") "ON SEMICONDUCTOR")
        (field (name "MANUFACTURER PART NUMBER") "BSS138L")
        (field (name "AUTHOR") "CERN DEM JLC")
      )
      (libsource (lib "ICs And Semiconductors") (part "N-MOSFET-D 1G 2S 3D"))
    )
    (comp (ref "T27")
      (value "BSS138LT1G")
      (footprint "SOT95P240X110-3N")
      (description "N-CHANNEL MOSFET WITH DIODE")
      (fields
        (field (name "MANUFACTURER") "ON SEMICONDUCTOR")
        (field (name "MANUFACTURER PART NUMBER") "BSS138L")
        (field (name "AUTHOR") "CERN DEM JLC")
      )
      (libsource (lib "ICs And Semiconductors") (part "N-MOSFET-D 1G 2S 3D"))
    )
    (comp (ref "T31")
      (value "BC847B")
      (footprint "SOT95P230X110-3N")
      (description "NPN Transistor")
      (fields (field (name "MANUFACTURER") "NXP SEMICONDUCTORS") (field (name "AUTHOR") "CERN DEM JLC"))
      (libsource (lib "ICs And Semiconductors") (part "NPN B1 E2 C3"))
    )
    (comp (ref "T32")
      (value "BC847B")
      (footprint "SOT95P230X110-3N")
      (description "NPN Transistor")
      (fields (field (name "MANUFACTURER") "NXP SEMICONDUCTORS") (field (name "AUTHOR") "CERN DEM JLC"))
      (libsource (lib "ICs And Semiconductors") (part "NPN B1 E2 C3"))
    )
  )
  (nets
    (net (code "1") (name "/ADC_Imon_1") (class "Default")
      (node (ref "C73") (pin "2") (pinfunction "2_2") (pintype "passive"))
      (node (ref "R90") (pin "2") (pinfunction "2_2") (pintype "passive"))
    )
    (net (code "2") (name "/ADC_Imon_2") (class "Default")
      (node (ref "C74") (pin "2") (pinfunction "2_2") (pintype "passive"))
      (node (ref "R91") (pin "2") (pinfunction "2_2") (pintype "passive"))
    )
    (net (code "3") (name "/ADC_TEMP_1") (class "Default")
      (node (ref "C72") (pin "2") (pinfunction "2_2") (pintype "passive"))
      (node (ref "R84") (pin "2") (pinfunction "2_2") (pintype "passive"))
    )
    (net (code "4") (name "/ADC_TEMP_2") (class "Default")
      (node (ref "C75") (pin "2") (pinfunction "2_2") (pintype "passive"))
      (node (ref "R92") (pin "2") (pinfunction "2_2") (pintype "passive"))
    )
    (net (code "5") (name "/CH1_P3V3") (class "Default")
      (node (ref "T22") (pin "1") (pinfunction "G_1") (pintype "passive"))
    )
    (net (code "6") (name "/CH1_P5V") (class "Default")
      (node (ref "T5") (pin "1") (pinfunction "G_1") (pintype "passive"))
    )
    (net (code "7") (name "/CH1_P6V") (class "Default")
      (node (ref "T21") (pin "1") (pinfunction "G_1") (pintype "passive"))
    )
    (net (code "8") (name "/CH1_P9V") (class "Default")
      (node (ref "T4") (pin "1") (pinfunction "G_1") (pintype "passive"))
    )
    (net (code "9") (name "/CH1_P12V") (class "Default")
      (node (ref "T3") (pin "1") (pinfunction "G_1") (pintype "passive"))
    )
    (net (code "10") (name "/CH1_P15V") (class "Default")
      (node (ref "T2") (pin "1") (pinfunction "G_1") (pintype "passive"))
    )
    (net (code "11") (name "/CH1_P18V") (class "Default")
      (node (ref "T1") (pin "1") (pinfunction "G_1") (pintype "passive"))
    )
    (net (code "12") (name "/CH1_PUser") (class "Default")
      (node (ref "T23") (pin "1") (pinfunction "G_1") (pintype "passive"))
    )
    (net (code "13") (name "/CH1_PVout") (class "Default")
      (node (ref "C71") (pin "2") (pinfunction "2_2") (pintype "passive"))
      (node (ref "R44") (pin "1") (pinfunction "1_1") (pintype "passive"))
      (node (ref "R49") (pin "2") (pinfunction "2_2") (pintype "passive"))
    )
    (net (code "14") (name "/CH2_P1V8") (class "Default")
      (node (ref "T25") (pin "1") (pinfunction "G_1") (pintype "passive"))
    )
    (net (code "15") (name "/CH2_P2V5") (class "Default")
      (node (ref "T24") (pin "1") (pinfunction "G_1") (pintype "passive"))
    )
    (net (code "16") (name "/CH2_P3V3") (class "Default")
      (node (ref "T9") (pin "1") (pinfunction "G_1") (pintype "passive"))
    )
    (net (code "17") (name "/CH2_P4V") (class "Default")
      (node (ref "T8") (pin "1") (pinfunction "G_1") (pintype "passive"))
    )
    (net (code "18") (name "/CH2_P5V") (class "Default")
      (node (ref "T7") (pin "1") (pinfunction "G_1") (pintype "passive"))
    )
    (net (code "19") (name "/CH2_P6V") (class "Default")
      (node (ref "T6") (pin "1") (pinfunction "G_1") (pintype "passive"))
    )
    (net (code "20") (name "/CH2_P9V") (class "Default")
      (node (ref "T27") (pin "1") (pinfunction "G_1") (pintype "passive"))
    )
    (net (code "21") (name "/CH2_P12V") (class "Default")
      (node (ref "T26") (pin "1") (pinfunction "G_1") (pintype "passive"))
    )
    (net (code "22") (name "/CH2_PVout") (class "Default")
      (node (ref "C76") (pin "2") (pinfunction "2_2") (pintype "passive"))
      (node (ref "R50") (pin "1") (pinfunction "1_1") (pintype "passive"))
      (node (ref "R51") (pin "2") (pinfunction "2_2") (pintype "passive"))
    )
    (net (code "23") (name "/En") (class "Default")
      (node (ref "IC3") (pin "1") (pinfunction "EN/UVLO_1") (pintype "passive"))
      (node (ref "IC5") (pin "1") (pinfunction "EN/UVLO_1") (pintype "passive"))
    )
    (net (code "24") (name "/Imon_1") (class "Default")
      (node (ref "IC6") (pin "10") (pinfunction "I_MON_10") (pintype "bidirectional"))
      (node (ref "R107") (pin "2") (pinfunction "2_2") (pintype "passive"))
      (node (ref "R90") (pin "1") (pinfunction "1_1") (pintype "passive"))
    )
    (net (code "25") (name "/Imon_2") (class "Default")
      (node (ref "IC4") (pin "10") (pinfunction "I_MON_10") (pintype "bidirectional"))
      (node (ref "R101") (pin "2") (pinfunction "2_2") (pintype "passive"))
      (node (ref "R91") (pin "1") (pinfunction "1_1") (pintype "passive"))
    )
    (net (code "26") (name "/TEMP_1") (class "Default")
      (node (ref "IC6") (pin "11") (pinfunction "TEMP_11") (pintype "bidirectional"))
      (node (ref "R23") (pin "2") (pinfunction "2_2") (pintype "passive"))
      (node (ref "R84") (pin "1") (pinfunction "1_1") (pintype "passive"))
    )
    (net (code "27") (name "/TEMP_2") (class "Default")
      (node (ref "IC4") (pin "11") (pinfunction "TEMP_11") (pintype "bidirectional"))
      (node (ref "R15") (pin "2") (pinfunction "2_2") (pintype "passive"))
      (node (ref "R92") (pin "1") (pinfunction "1_1") (pintype "passive"))
    )
    (net (code "28") (name "GND") (class "Default")
      (node (ref "C18") (pin "1") (pinfunction "1_1") (pintype "passive"))
      (node (ref "C19") (pin "1") (pinfunction "1_1") (pintype "passive"))
      (node (ref "C20") (pin "1") (pinfunction "1_1") (pintype "passive"))
      (node (ref "C21") (pin "1") (pinfunction "1_1") (pintype "passive"))
      (node (ref "C22") (pin "1") (pinfunction "1_1") (pintype "passive"))
      (node (ref "C23") (pin "1") (pinfunction "1_1") (pintype "passive"))
      (node (ref "C24") (pin "1") (pinfunction "1_1") (pintype "passive"))
      (node (ref "C27") (pin "1") (pinfunction "1_1") (pintype "passive"))
      (node (ref "C28") (pin "2") (pinfunction "2_2") (pintype "passive"))
      (node (ref "C29") (pin "1") (pinfunction "1_1") (pintype "passive"))
      (node (ref "C30") (pin "1") (pinfunction "1_1") (pintype "passive"))
      (node (ref "C31") (pin "1") (pinfunction "1_1") (pintype "passive"))
      (node (ref "C32") (pin "1") (pinfunction "1_1") (pintype "passive"))
      (node (ref "C33") (pin "1") (pinfunction "1_1") (pintype "passive"))
      (node (ref "C34") (pin "1") (pinfunction "1_1") (pintype "passive"))
      (node (ref "C35") (pin "1") (pinfunction "1_1") (pintype "passive"))
      (node (ref "C36") (pin "1") (pinfunction "1_1") (pintype "passive"))
      (node (ref "C37") (pin "1") (pinfunction "1_1") (pintype "passive"))
      (node (ref "C38") (pin "1") (pinfunction "1_1") (pintype "passive"))
      (node (ref "C39") (pin "1") (pinfunction "1_1") (pintype "passive"))
      (node (ref "C40") (pin "1") (pinfunction "1_1") (pintype "passive"))
      (node (ref "C41") (pin "1") (pinfunction "1_1") (pintype "passive"))
      (node (ref "C44") (pin "1") (pinfunction "1_1") (pintype "passive"))
      (node (ref "C45") (pin "2") (pinfunction "2_2") (pintype "passive"))
      (node (ref "C46") (pin "1") (pinfunction "1_1") (pintype "passive"))
      (node (ref "C47") (pin "1") (pinfunction "1_1") (pintype "passive"))
      (node (ref "C48") (pin "1") (pinfunction "1_1") (pintype "passive"))
      (node (ref "C49") (pin "1") (pinfunction "1_1") (pintype "passive"))
      (node (ref "C50") (pin "1") (pinfunction "1_1") (pintype "passive"))
      (node (ref "C51") (pin "1") (pinfunction "1_1") (pintype "passive"))
      (node (ref "C66") (pin "1") (pinfunction "1_1") (pintype "passive"))
      (node (ref "C67") (pin "1") (pinfunction "1_1") (pintype "passive"))
      (node (ref "C71") (pin "1") (pinfunction "1_1") (pintype "passive"))
      (node (ref "C72") (pin "1") (pinfunction "1_1") (pintype "passive"))
      (node (ref "C73") (pin "1") (pinfunction "1_1") (pintype "passive"))
      (node (ref "C74") (pin "1") (pinfunction "1_1") (pintype "passive"))
      (node (ref "C75") (pin "1") (pinfunction "1_1") (pintype "passive"))
      (node (ref "C76") (pin "1") (pinfunction "1_1") (pintype "passive"))
      (node (ref "C84") (pin "2") (pinfunction "2_2") (pintype "passive"))
      (node (ref "C85") (pin "2") (pinfunction "2_2") (pintype "passive"))
      (node (ref "IC3") (pin "11") (pinfunction "PGND_11") (pintype "passive"))
      (node (ref "IC3") (pin "4") (pinfunction "BIAS_4") (pintype "passive"))
      (node (ref "IC3") (pin "9") (pinfunction "MODE_9") (pintype "passive"))
      (node (ref "IC5") (pin "11") (pinfunction "PGND_11") (pintype "passive"))
      (node (ref "IC5") (pin "4") (pinfunction "BIAS_4") (pintype "passive"))
      (node (ref "IC5") (pin "9") (pinfunction "MODE_9") (pintype "passive"))
      (node (ref "L5") (pin "1") (pinfunction "1_1") (pintype "passive"))
      (node (ref "L8") (pin "1") (pinfunction "1_1") (pintype "passive"))
      (node (ref "R100") (pin "1") (pinfunction "1_1") (pintype "passive"))
      (node (ref "R102") (pin "1") (pinfunction "1_1") (pintype "passive"))
      (node (ref "R103") (pin "1") (pinfunction "1_1") (pintype "passive"))
      (node (ref "R109") (pin "1") (pinfunction "1_1") (pintype "passive"))
      (node (ref "R110") (pin "1") (pinfunction "1_1") (pintype "passive"))
      (node (ref "R13") (pin "1") (pinfunction "1_1") (pintype "passive"))
      (node (ref "R15") (pin "1") (pinfunction "1_1") (pintype "passive"))
      (node (ref "R18") (pin "1") (pinfunction "1_1") (pintype "passive"))
      (node (ref "R23") (pin "1") (pinfunction "1_1") (pintype "passive"))
      (node (ref "R33") (pin "1") (pinfunction "1_1") (pintype "passive"))
      (node (ref "R34") (pin "1") (pinfunction "1_1") (pintype "passive"))
      (node (ref "R49") (pin "1") (pinfunction "1_1") (pintype "passive"))
      (node (ref "R51") (pin "1") (pinfunction "1_1") (pintype "passive"))
      (node (ref "R69") (pin "1") (pinfunction "1_1") (pintype "passive"))
      (node (ref "R88") (pin "1") (pinfunction "1_1") (pintype "passive"))
      (node (ref "T1") (pin "2") (pinfunction "S_2") (pintype "passive"))
      (node (ref "T2") (pin "2") (pinfunction "S_2") (pintype "passive"))
      (node (ref "T21") (pin "2") (pinfunction "S_2") (pintype "passive"))
      (node (ref "T22") (pin "2") (pinfunction "S_2") (pintype "passive"))
      (node (ref "T23") (pin "2") (pinfunction "S_2") (pintype "passive"))
      (node (ref "T24") (pin "2") (pinfunction "S_2") (pintype "passive"))
      (node (ref "T25") (pin "2") (pinfunction "S_2") (pintype "passive"))
      (node (ref "T26") (pin "2") (pinfunction "S_2") (pintype "passive"))
      (node (ref "T27") (pin "2") (pinfunction "S_2") (pintype "passive"))
      (node (ref "T3") (pin "2") (pinfunction "S_2") (pintype "passive"))
      (node (ref "T4") (pin "2") (pinfunction "S_2") (pintype "passive"))
      (node (ref "T5") (pin "2") (pinfunction "S_2") (pintype "passive"))
      (node (ref "T6") (pin "2") (pinfunction "S_2") (pintype "passive"))
      (node (ref "T7") (pin "2") (pinfunction "S_2") (pintype "passive"))
      (node (ref "T8") (pin "2") (pinfunction "S_2") (pintype "passive"))
      (node (ref "T9") (pin "2") (pinfunction "S_2") (pintype "passive"))
    )
    (net (code "29") (name "Net-(C32-Pad2)") (class "Default")
      (node (ref "C32") (pin "2") (pinfunction "2_2") (pintype "passive"))
      (node (ref "R17") (pin "1") (pinfunction "1_1") (pintype "passive"))
    )
    (net (code "30") (name "Net-(C49-Pad2)") (class "Default")
      (node (ref "C49") (pin "2") (pinfunction "2_2") (pintype "passive"))
      (node (ref "R25") (pin "1") (pinfunction "1_1") (pintype "passive"))
    )
    (net (code "31") (name "Net-(D2-A)") (class "Default")
      (node (ref "C26") (pin "2") (pinfunction "2_2") (pintype "passive"))
      (node (ref "D2") (pin "2") (pinfunction "A_2") (pintype "passive"))
      (node (ref "L5") (pin "3") (pinfunction "3_3") (pintype "passive"))
    )
    (net (code "32") (name "Net-(D2-C)") (class "Default")
      (node (ref "C19") (pin "2") (pinfunction "2_2") (pintype "passive"))
      (node (ref "C20") (pin "2") (pinfunction "2_2") (pintype "passive"))
      (node (ref "C25") (pin "2") (pinfunction "2_2") (pintype "passive"))
      (node (ref "D2") (pin "1") (pinfunction "C_1") (pintype "passive"))
      (node (ref "L12") (pin "1") (pinfunction "1_1") (pintype "passive"))
      (node (ref "R14") (pin "2") (pinfunction "2_2") (pintype "passive"))
    )
    (net (code "33") (name "Net-(D3-A)") (class "Default")
      (node (ref "C42") (pin "2") (pinfunction "2_2") (pintype "passive"))
      (node (ref "D3") (pin "2") (pinfunction "A_2") (pintype "passive"))
      (node (ref "L8") (pin "3") (pinfunction "3_3") (pintype "passive"))
    )
    (net (code "34") (name "Net-(D3-C)") (class "Default")
      (node (ref "C36") (pin "2") (pinfunction "2_2") (pintype "passive"))
      (node (ref "C37") (pin "2") (pinfunction "2_2") (pintype "passive"))
      (node (ref "C43") (pin "2") (pinfunction "2_2") (pintype "passive"))
      (node (ref "D3") (pin "1") (pinfunction "C_1") (pintype "passive"))
      (node (ref "L11") (pin "1") (pinfunction "1_1") (pintype "passive"))
      (node (ref "R24") (pin "2") (pinfunction "2_2") (pintype "passive"))
    )
    (net (code "35") (name "Net-(IC3-FBX)") (class "Default")
      (node (ref "IC3") (pin "6") (pinfunction "FBX_6") (pintype "passive"))
      (node (ref "R18") (pin "2") (pinfunction "2_2") (pintype "passive"))
      (node (ref "T16") (pin "3") (pinfunction "C_3") (pintype "passive"))
    )
    (net (code "36") (name "Net-(IC3-INTVcc)") (class "Default")
      (node (ref "C34") (pin "2") (pinfunction "2_2") (pintype "passive"))
      (node (ref "IC3") (pin "3") (pinfunction "INTVcc_3") (pintype "passive"))
    )
    (net (code "37") (name "Net-(IC3-RT)") (class "Default")
      (node (ref "IC3") (pin "7") (pinfunction "RT_7") (pintype "passive"))
      (node (ref "R34") (pin "2") (pinfunction "2_2") (pintype "passive"))
    )
    (net (code "38") (name "Net-(IC3-SS)") (class "Default")
      (node (ref "C33") (pin "2") (pinfunction "2_2") (pintype "passive"))
      (node (ref "IC3") (pin "8") (pinfunction "SS_8") (pintype "passive"))
    )
    (net (code "39") (name "Net-(IC3-SW)") (class "Default")
      (node (ref "C26") (pin "1") (pinfunction "1_1") (pintype "passive"))
      (node (ref "IC3") (pin "10") (pinfunction "SW_10") (pintype "passive"))
      (node (ref "L5") (pin "4") (pinfunction "4_4") (pintype "passive"))
    )
    (net (code "40") (name "Net-(IC3-VIN)") (class "Default")
      (node (ref "C28") (pin "1") (pinfunction "1_1") (pintype "passive"))
      (node (ref "C29") (pin "2") (pinfunction "2_2") (pintype "passive"))
      (node (ref "C30") (pin "2") (pinfunction "2_2") (pintype "passive"))
      (node (ref "IC3") (pin "2") (pinfunction "VIN_2") (pintype "passive"))
      (node (ref "L5") (pin "2") (pinfunction "2_2") (pintype "passive"))
      (node (ref "L6") (pin "2") (pinfunction "2_2") (pintype "passive"))
    )
    (net (code "41") (name "Net-(IC3-Vc)") (class "Default")
      (node (ref "IC3") (pin "5") (pinfunction "Vc_5") (pintype "passive"))
      (node (ref "R17") (pin "2") (pinfunction "2_2") (pintype "passive"))
    )
    (net (code "42") (name "Net-(IC4-IN_1)") (class "Default")
      (node (ref "C21") (pin "2") (pinfunction "2_2") (pintype "passive"))
      (node (ref "C22") (pin "2") (pinfunction "2_2") (pintype "passive"))
      (node (ref "C67") (pin "2") (pinfunction "2_2") (pintype "passive"))
      (node (ref "C85") (pin "1") (pinfunction "1_1") (pintype "passive"))
      (node (ref "IC4") (pin "12") (pinfunction "IN_1_12") (pintype "power_in"))
      (node (ref "IC4") (pin "13") (pinfunction "IN_2_13") (pintype "power_in"))
      (node (ref "IC4") (pin "14") (pinfunction "IN_3_14") (pintype "power_in"))
      (node (ref "IC4") (pin "15") (pinfunction "IN_4_15") (pintype "power_in"))
      (node (ref "L15") (pin "2") (pinfunction "2_2") (pintype "passive"))
    )
    (net (code "43") (name "Net-(IC4-I_LIM)") (class "Default")
      (node (ref "IC4") (pin "6") (pinfunction "I_LIM_6") (pintype "bidirectional"))
      (node (ref "R106") (pin "1") (pinfunction "1_1") (pintype "passive"))
    )
    (net (code "44") (name "Net-(IC4-OUT_1)") (class "Default")
      (node (ref "C23") (pin "2") (pinfunction "2_2") (pintype "passive"))
      (node (ref "C24") (pin "2") (pinfunction "2_2") (pintype "passive"))
      (node (ref "IC4") (pin "1") (pinfunction "OUT_1_1") (pintype "power_in"))
      (node (ref "IC4") (pin "16") (pinfunction "OUT_8_16") (pintype "power_in"))
      (node (ref "IC4") (pin "17") (pinfunction "OUT_9_17") (pintype "power_in"))
      (node (ref "IC4") (pin "2") (pinfunction "OUT_2_2") (pintype "power_in"))
      (node (ref "IC4") (pin "3") (pinfunction "OUT_3_3") (pintype "power_in"))
      (node (ref "IC4") (pin "4") (pinfunction "OUT_4_4") (pintype "power_in"))
      (node (ref "IC4") (pin "5") (pinfunction "OUT_5_5") (pintype "power_in"))
      (node (ref "IC4") (pin "8") (pinfunction "OUT_6_8") (pintype "power_in"))
      (node (ref "IC4") (pin "9") (pinfunction "OUT_7_9") (pintype "power_in"))
      (node (ref "L4") (pin "1") (pinfunction "1_1") (pintype "passive"))
      (node (ref "R103") (pin "2") (pinfunction "2_2") (pintype "passive"))
      (node (ref "R106") (pin "2") (pinfunction "2_2") (pintype "passive"))
      (node (ref "R16") (pin "2") (pinfunction "2_2") (pintype "passive"))
      (node (ref "R50") (pin "2") (pinfunction "2_2") (pintype "passive"))
      (node (ref "T32") (pin "3") (pinfunction "C_3") (pintype "passive"))
    )
    (net (code "45") (name "Net-(IC4-SET)") (class "Default")
      (node (ref "C31") (pin "2") (pinfunction "2_2") (pintype "passive"))
      (node (ref "IC4") (pin "7") (pinfunction "SET_7") (pintype "bidirectional"))
      (node (ref "R104") (pin "2") (pinfunction "2_2") (pintype "passive"))
      (node (ref "R105") (pin "2") (pinfunction "2_2") (pintype "passive"))
      (node (ref "R21") (pin "2") (pinfunction "2_2") (pintype "passive"))
      (node (ref "R59") (pin "2") (pinfunction "2_2") (pintype "passive"))
      (node (ref "R60") (pin "2") (pinfunction "2_2") (pintype "passive"))
      (node (ref "R61") (pin "2") (pinfunction "2_2") (pintype "passive"))
      (node (ref "R87") (pin "2") (pinfunction "2_2") (pintype "passive"))
      (node (ref "R89") (pin "2") (pinfunction "2_2") (pintype "passive"))
    )
    (net (code "46") (name "Net-(IC5-FBX)") (class "Default")
      (node (ref "IC5") (pin "6") (pinfunction "FBX_6") (pintype "passive"))
      (node (ref "R13") (pin "2") (pinfunction "2_2") (pintype "passive"))
      (node (ref "T17") (pin "3") (pinfunction "C_3") (pintype "passive"))
    )
    (net (code "47") (name "Net-(IC5-INTVcc)") (class "Default")
      (node (ref "C51") (pin "2") (pinfunction "2_2") (pintype "passive"))
      (node (ref "IC5") (pin "3") (pinfunction "INTVcc_3") (pintype "passive"))
    )
    (net (code "48") (name "Net-(IC5-RT)") (class "Default")
      (node (ref "IC5") (pin "7") (pinfunction "RT_7") (pintype "passive"))
      (node (ref "R33") (pin "2") (pinfunction "2_2") (pintype "passive"))
    )
    (net (code "49") (name "Net-(IC5-SS)") (class "Default")
      (node (ref "C50") (pin "2") (pinfunction "2_2") (pintype "passive"))
      (node (ref "IC5") (pin "8") (pinfunction "SS_8") (pintype "passive"))
    )
    (net (code "50") (name "Net-(IC5-SW)") (class "Default")
      (node (ref "C42") (pin "1") (pinfunction "1_1") (pintype "passive"))
      (node (ref "IC5") (pin "10") (pinfunction "SW_10") (pintype "passive"))
      (node (ref "L8") (pin "4") (pinfunction "4_4") (pintype "passive"))
    )
    (net (code "51") (name "Net-(IC5-VIN)") (class "Default")
      (node (ref "C45") (pin "1") (pinfunction "1_1") (pintype "passive"))
      (node (ref "C46") (pin "2") (pinfunction "2_2") (pintype "passive"))
      (node (ref "C47") (pin "2") (pinfunction "2_2") (pintype "passive"))
      (node (ref "IC5") (pin "2") (pinfunction "VIN_2") (pintype "passive"))
      (node (ref "L8") (pin "2") (pinfunction "2_2") (pintype "passive"))
      (node (ref "L9") (pin "2") (pinfunction "2_2") (pintype "passive"))
    )
    (net (code "52") (name "Net-(IC5-Vc)") (class "Default")
      (node (ref "IC5") (pin "5") (pinfunction "Vc_5") (pintype "passive"))
      (node (ref "R25") (pin "2") (pinfunction "2_2") (pintype "passive"))
    )
    (net (code "53") (name "Net-(IC6-IN_1)") (class "Default")
      (node (ref "C38") (pin "2") (pinfunction "2_2") (pintype "passive"))
      (node (ref "C39") (pin "2") (pinfunction "2_2") (pintype "passive"))
      (node (ref "C66") (pin "2") (pinfunction "2_2") (pintype "passive"))
      (node (ref "C84") (pin "1") (pinfunction "1_1") (pintype "passive"))
      (node (ref "IC6") (pin "12") (pinfunction "IN_1_12") (pintype "power_in"))
      (node (ref "IC6") (pin "13") (pinfunction "IN_2_13") (pintype "power_in"))
      (node (ref "IC6") (pin "14") (pinfunction "IN_3_14") (pintype "power_in"))
      (node (ref "IC6") (pin "15") (pinfunction "IN_4_15") (pintype "power_in"))
      (node (ref "L14") (pin "2") (pinfunction "2_2") (pintype "passive"))
    )
    (net (code "54") (name "Net-(IC6-I_LIM)") (class "Default")
      (node (ref "IC6") (pin "6") (pinfunction "I_LIM_6") (pintype "bidirectional"))
      (node (ref "R99") (pin "1") (pinfunction "1_1") (pintype "passive"))
    )
    (net (code "55") (name "Net-(IC6-OUT_1)") (class "Default")
      (node (ref "C40") (pin "2") (pinfunction "2_2") (pintype "passive"))
      (node (ref "C41") (pin "2") (pinfunction "2_2") (pintype "passive"))
      (node (ref "IC6") (pin "1") (pinfunction "OUT_1_1") (pintype "power_in"))
      (node (ref "IC6") (pin "16") (pinfunction "OUT_8_16") (pintype "power_in"))
      (node (ref "IC6") (pin "17") (pinfunction "OUT_9_17") (pintype "power_in"))
      (node (ref "IC6") (pin "2") (pinfunction "OUT_2_2") (pintype "power_in"))
      (node (ref "IC6") (pin "3") (pinfunction "OUT_3_3") (pintype "power_in"))
      (node (ref "IC6") (pin "4") (pinfunction "OUT_4_4") (pintype "power_in"))
      (node (ref "IC6") (pin "5") (pinfunction "OUT_5_5") (pintype "power_in"))
      (node (ref "IC6") (pin "8") (pinfunction "OUT_6_8") (pintype "power_in"))
      (node (ref "IC6") (pin "9") (pinfunction "OUT_7_9") (pintype "power_in"))
      (node (ref "L7") (pin "1") (pinfunction "1_1") (pintype "passive"))
      (node (ref "R27") (pin "2") (pinfunction "2_2") (pintype "passive"))
      (node (ref "R44") (pin "2") (pinfunction "2_2") (pintype "passive"))
      (node (ref "R99") (pin "2") (pinfunction "2_2") (pintype "passive"))
      (node (ref "T31") (pin "3") (pinfunction "C_3") (pintype "passive"))
    )
    (net (code "56") (name "Net-(IC6-SET)") (class "Default")
      (node (ref "C48") (pin "2") (pinfunction "2_2") (pintype "passive"))
      (node (ref "IC6") (pin "7") (pinfunction "SET_7") (pintype "bidirectional"))
      (node (ref "R113") (pin "2") (pinfunction "2_2") (pintype "passive"))
      (node (ref "R20") (pin "2") (pinfunction "2_2") (pintype "passive"))
      (node (ref "R22") (pin "2") (pinfunction "2_2") (pintype "passive"))
      (node (ref "R29") (pin "2") (pinfunction "2_2") (pintype "passive"))
      (node (ref "R30") (pin "2") (pinfunction "2_2") (pintype "passive"))
      (node (ref "R31") (pin "2") (pinfunction "2_2") (pintype "passive"))
      (node (ref "R32") (pin "2") (pinfunction "2_2") (pintype "passive"))
      (node (ref "R39") (pin "2") (pinfunction "2_2") (pintype "passive"))
    )
    (net (code "57") (name "Net-(L11-Pad2)") (class "Default")
      (node (ref "L11") (pin "2") (pinfunction "2_2") (pintype "passive"))
      (node (ref "L14") (pin "1") (pinfunction "1_1") (pintype "passive"))
    )
    (net (code "58") (name "Net-(L12-Pad2)") (class "Default")
      (node (ref "L12") (pin "2") (pinfunction "2_2") (pintype "passive"))
      (node (ref "L15") (pin "1") (pinfunction "1_1") (pintype "passive"))
    )
    (net (code "59") (name "Net-(P2-CCW)") (class "Default")
      (node (ref "P2") (pin "1") (pinfunction "CCW_1") (pintype "passive"))
      (node (ref "P2") (pin "2") (pinfunction "W_2") (pintype "passive"))
      (node (ref "R112") (pin "2") (pinfunction "2_2") (pintype "passive"))
      (node (ref "R32") (pin "1") (pinfunction "1_1") (pintype "passive"))
    )
    (net (code "60") (name "Net-(P2-CW)") (class "Default")
      (node (ref "P2") (pin "3") (pinfunction "CW_3") (pintype "passive"))
      (node (ref "R112") (pin "1") (pinfunction "1_1") (pintype "passive"))
      (node (ref "T23") (pin "3") (pinfunction "D_3") (pintype "passive"))
    )
    (net (code "61") (name "Net-(R100-Pad2)") (class "Default")
      (node (ref "R100") (pin "2") (pinfunction "2_2") (pintype "passive"))
      (node (ref "R101") (pin "1") (pinfunction "1_1") (pintype "passive"))
    )
    (net (code "62") (name "Net-(R107-Pad1)") (class "Default")
      (node (ref "R107") (pin "1") (pinfunction "1_1") (pintype "passive"))
      (node (ref "R69") (pin "2") (pinfunction "2_2") (pintype "passive"))
    )
    (net (code "63") (name "Net-(R113-Pad1)") (class "Default")
      (node (ref "R113") (pin "1") (pinfunction "1_1") (pintype "passive"))
      (node (ref "R114") (pin "1") (pinfunction "1_1") (pintype "passive"))
    )
    (net (code "64") (name "Net-(T1-D)") (class "Default")
      (node (ref "R114") (pin "2") (pinfunction "2_2") (pintype "passive"))
      (node (ref "T1") (pin "3") (pinfunction "D_3") (pintype "passive"))
    )
    (net (code "65") (name "Net-(T2-D)") (class "Default")
      (node (ref "R20") (pin "1") (pinfunction "1_1") (pintype "passive"))
      (node (ref "T2") (pin "3") (pinfunction "D_3") (pintype "passive"))
    )
    (net (code "66") (name "Net-(T3-D)") (class "Default")
      (node (ref "R22") (pin "1") (pinfunction "1_1") (pintype "passive"))
      (node (ref "T3") (pin "3") (pinfunction "D_3") (pintype "passive"))
    )
    (net (code "67") (name "Net-(T4-D)") (class "Default")
      (node (ref "R39") (pin "1") (pinfunction "1_1") (pintype "passive"))
      (node (ref "T4") (pin "3") (pinfunction "D_3") (pintype "passive"))
    )
    (net (code "68") (name "Net-(T5-D)") (class "Default")
      (node (ref "R30") (pin "1") (pinfunction "1_1") (pintype "passive"))
      (node (ref "T5") (pin "3") (pinfunction "D_3") (pintype "passive"))
    )
    (net (code "69") (name "Net-(T6-D)") (class "Default")
      (node (ref "R60") (pin "1") (pinfunction "1_1") (pintype "passive"))
      (node (ref "T6") (pin "3") (pinfunction "D_3") (pintype "passive"))
    )
    (net (code "70") (name "Net-(T7-D)") (class "Default")
      (node (ref "R61") (pin "1") (pinfunction "1_1") (pintype "passive"))
      (node (ref "T7") (pin "3") (pinfunction "D_3") (pintype "passive"))
    )
    (net (code "71") (name "Net-(T8-D)") (class "Default")
      (node (ref "R21") (pin "1") (pinfunction "1_1") (pintype "passive"))
      (node (ref "T8") (pin "3") (pinfunction "D_3") (pintype "passive"))
    )
    (net (code "72") (name "Net-(T9-D)") (class "Default")
      (node (ref "R87") (pin "1") (pinfunction "1_1") (pintype "passive"))
      (node (ref "T9") (pin "3") (pinfunction "D_3") (pintype "passive"))
    )
    (net (code "73") (name "Net-(T16-B)") (class "Default")
      (node (ref "R16") (pin "1") (pinfunction "1_1") (pintype "passive"))
      (node (ref "T16") (pin "1") (pinfunction "B_1") (pintype "passive"))
    )
    (net (code "74") (name "Net-(T16-E)") (class "Default")
      (node (ref "C25") (pin "1") (pinfunction "1_1") (pintype "passive"))
      (node (ref "R14") (pin "1") (pinfunction "1_1") (pintype "passive"))
      (node (ref "T16") (pin "2") (pinfunction "E_2") (pintype "passive"))
    )
    (net (code "75") (name "Net-(T17-B)") (class "Default")
      (node (ref "R27") (pin "1") (pinfunction "1_1") (pintype "passive"))
      (node (ref "T17") (pin "1") (pinfunction "B_1") (pintype "passive"))
    )
    (net (code "76") (name "Net-(T17-E)") (class "Default")
      (node (ref "C43") (pin "1") (pinfunction "1_1") (pintype "passive"))
      (node (ref "R24") (pin "1") (pinfunction "1_1") (pintype "passive"))
      (node (ref "T17") (pin "2") (pinfunction "E_2") (pintype "passive"))
    )
    (net (code "77") (name "Net-(T21-D)") (class "Default")
      (node (ref "R29") (pin "1") (pinfunction "1_1") (pintype "passive"))
      (node (ref "T21") (pin "3") (pinfunction "D_3") (pintype "passive"))
    )
    (net (code "78") (name "Net-(T22-D)") (class "Default")
      (node (ref "R31") (pin "1") (pinfunction "1_1") (pintype "passive"))
      (node (ref "T22") (pin "3") (pinfunction "D_3") (pintype "passive"))
    )
    (net (code "79") (name "Net-(T24-D)") (class "Default")
      (node (ref "R104") (pin "1") (pinfunction "1_1") (pintype "passive"))
      (node (ref "T24") (pin "3") (pinfunction "D_3") (pintype "passive"))
    )
    (net (code "80") (name "Net-(T25-D)") (class "Default")
      (node (ref "R105") (pin "1") (pinfunction "1_1") (pintype "passive"))
      (node (ref "T25") (pin "3") (pinfunction "D_3") (pintype "passive"))
    )
    (net (code "81") (name "Net-(T26-D)") (class "Default")
      (node (ref "R59") (pin "1") (pinfunction "1_1") (pintype "passive"))
      (node (ref "T26") (pin "3") (pinfunction "D_3") (pintype "passive"))
    )
    (net (code "82") (name "Net-(T27-D)") (class "Default")
      (node (ref "R89") (pin "1") (pinfunction "1_1") (pintype "passive"))
      (node (ref "T27") (pin "3") (pinfunction "D_3") (pintype "passive"))
    )
    (net (code "83") (name "Net-(T31-B)") (class "Default")
      (node (ref "R26") (pin "1") (pinfunction "1_1") (pintype "passive"))
      (node (ref "R88") (pin "2") (pinfunction "2_2") (pintype "passive"))
      (node (ref "T31") (pin "1") (pinfunction "B_1") (pintype "passive"))
    )
    (net (code "84") (name "Net-(T31-E)") (class "Default")
      (node (ref "R102") (pin "2") (pinfunction "2_2") (pintype "passive"))
      (node (ref "T31") (pin "2") (pinfunction "E_2") (pintype "passive"))
    )
    (net (code "85") (name "Net-(T32-B)") (class "Default")
      (node (ref "R108") (pin "1") (pinfunction "1_1") (pintype "passive"))
      (node (ref "R109") (pin "2") (pinfunction "2_2") (pintype "passive"))
      (node (ref "T32") (pin "1") (pinfunction "B_1") (pintype "passive"))
    )
    (net (code "86") (name "Net-(T32-E)") (class "Default")
      (node (ref "R110") (pin "2") (pinfunction "2_2") (pintype "passive"))
      (node (ref "T32") (pin "2") (pinfunction "E_2") (pintype "passive"))
    )
    (net (code "87") (name "P3V3i") (class "Default")
      (node (ref "R108") (pin "2") (pinfunction "2_2") (pintype "passive"))
      (node (ref "R26") (pin "2") (pinfunction "2_2") (pintype "passive"))
    )
    (net (code "88") (name "P12V0") (class "Default")
      (node (ref "C27") (pin "2") (pinfunction "2_2") (pintype "passive"))
      (node (ref "C44") (pin "2") (pinfunction "2_2") (pintype "passive"))
      (node (ref "L6") (pin "1") (pinfunction "1_1") (pintype "passive"))
      (node (ref "L9") (pin "1") (pinfunction "1_1") (pintype "passive"))
    )
    (net (code "89") (name "Pos_CH1") (class "Default")
      (node (ref "C35") (pin "2") (pinfunction "2_2") (pintype "passive"))
      (node (ref "L7") (pin "2") (pinfunction "2_2") (pintype "passive"))
    )
    (net (code "90") (name "Pos_CH2") (class "Default")
      (node (ref "C18") (pin "2") (pinfunction "2_2") (pintype "passive"))
      (node (ref "L4") (pin "2") (pinfunction "2_2") (pintype "passive"))
    )
  )
)
